# mmt_xbee.net
KiCad netlist of a schematic drawn in EAGLE
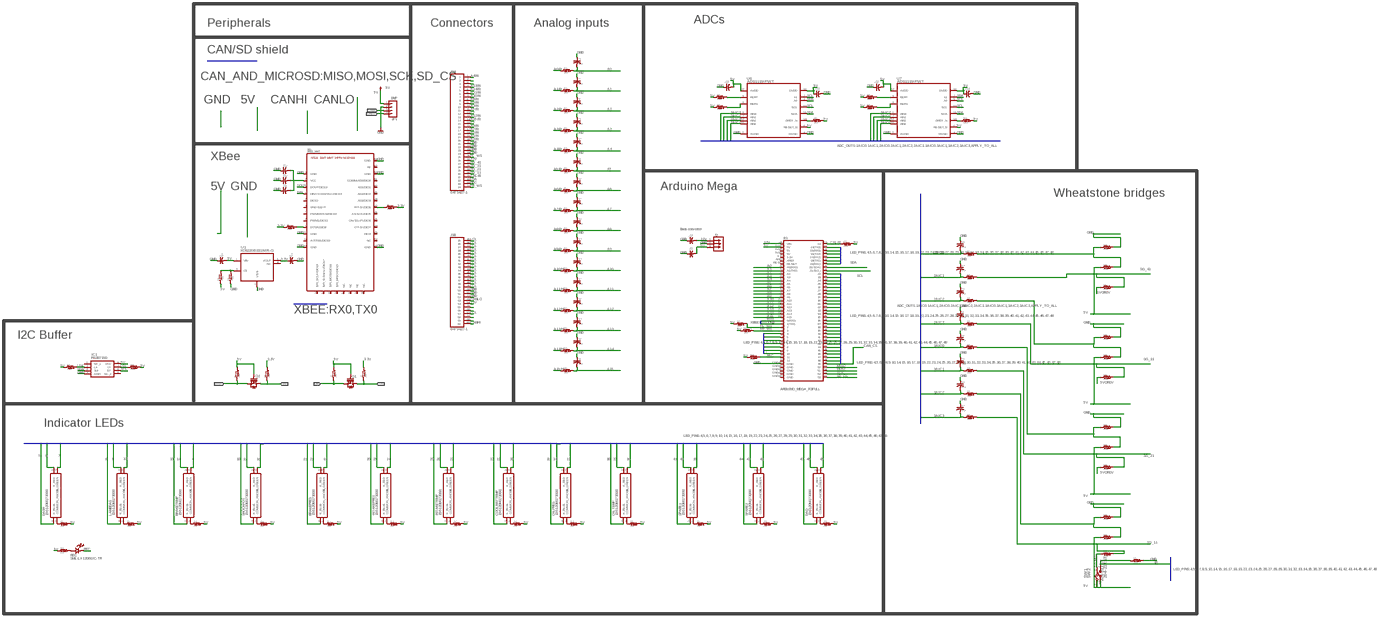
[diagram p0: schematic, sheet 1, overview]
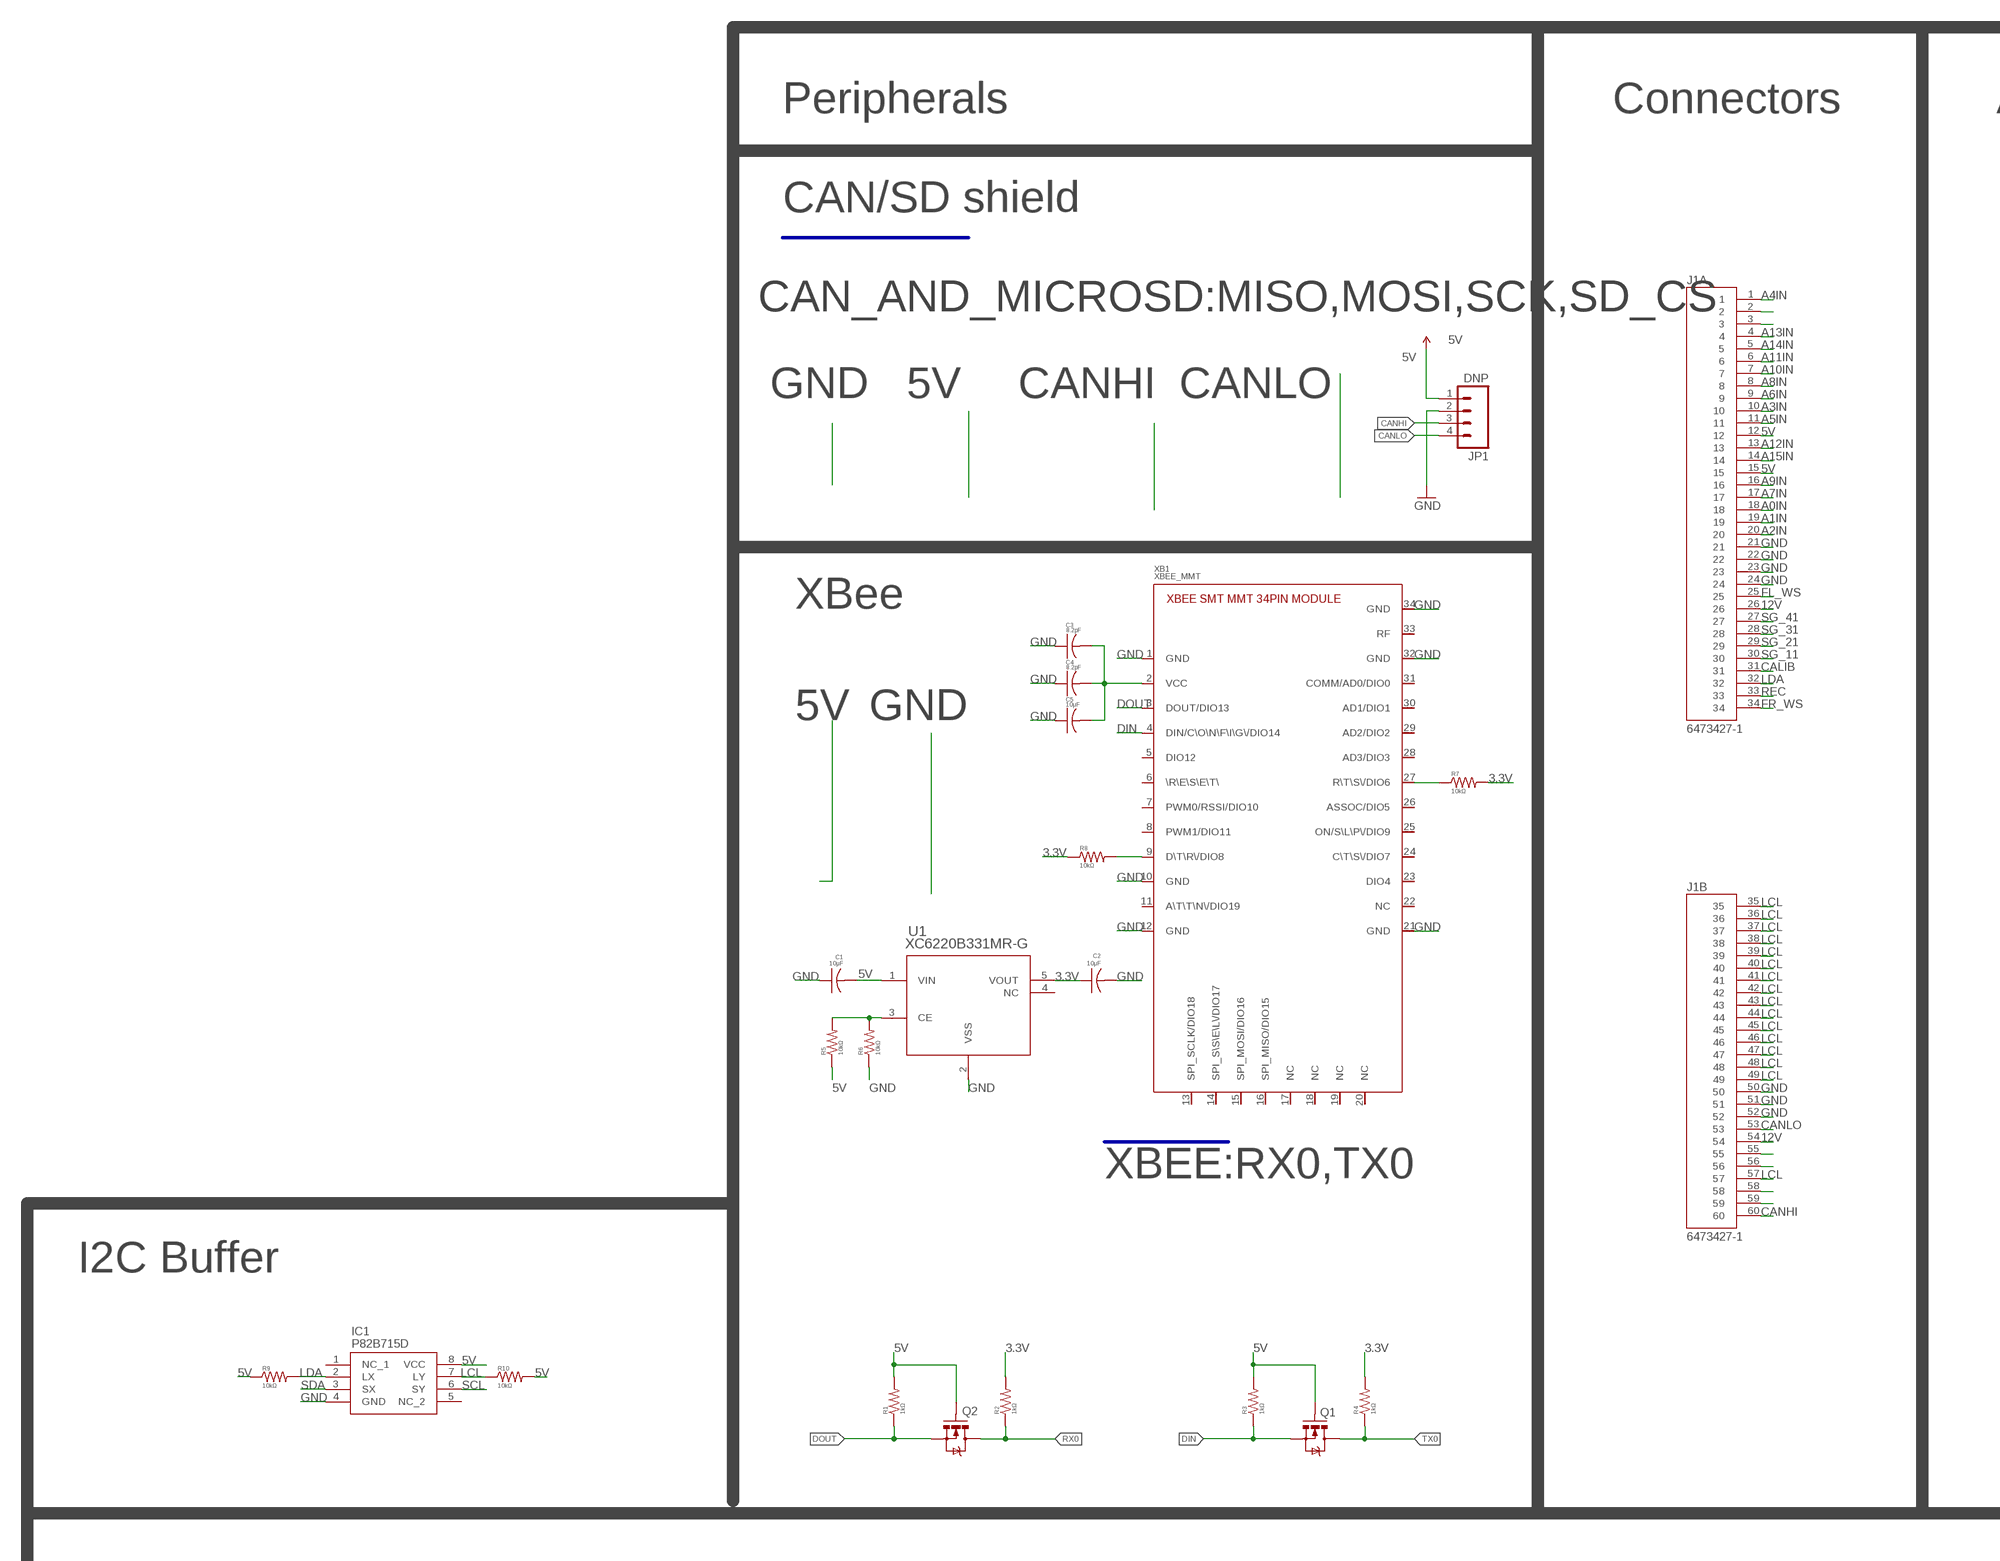
[diagram p1: schematic, sheet 1, part 1 of 5]
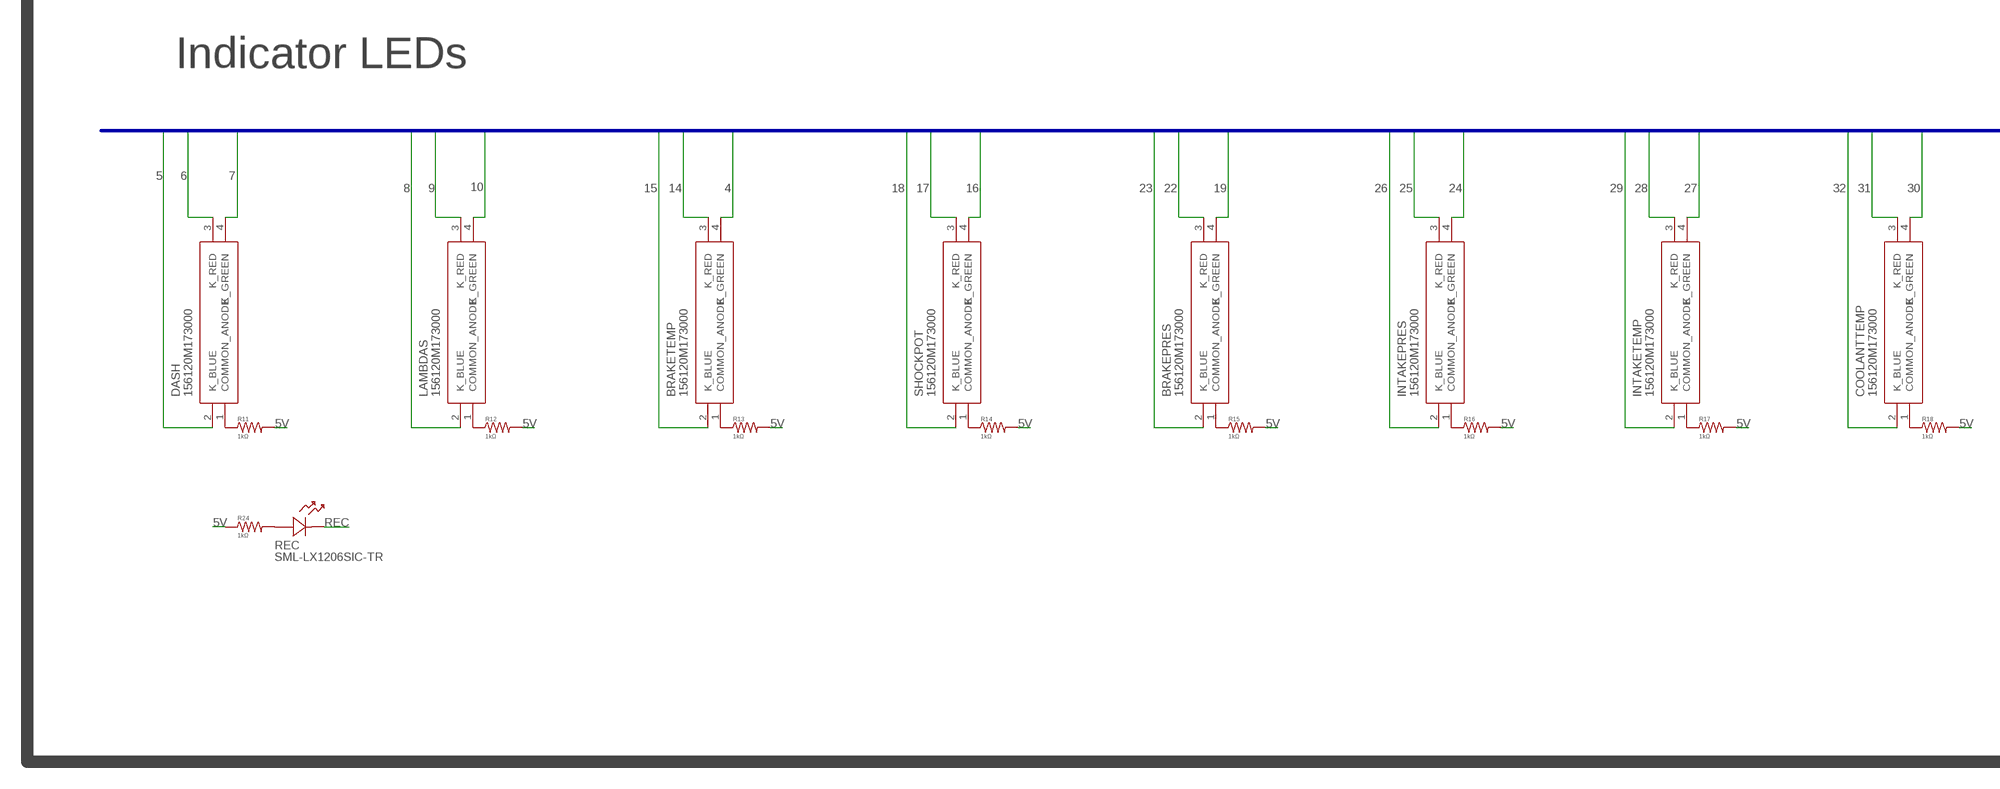
[diagram p2: schematic, sheet 1, part 2 of 5]
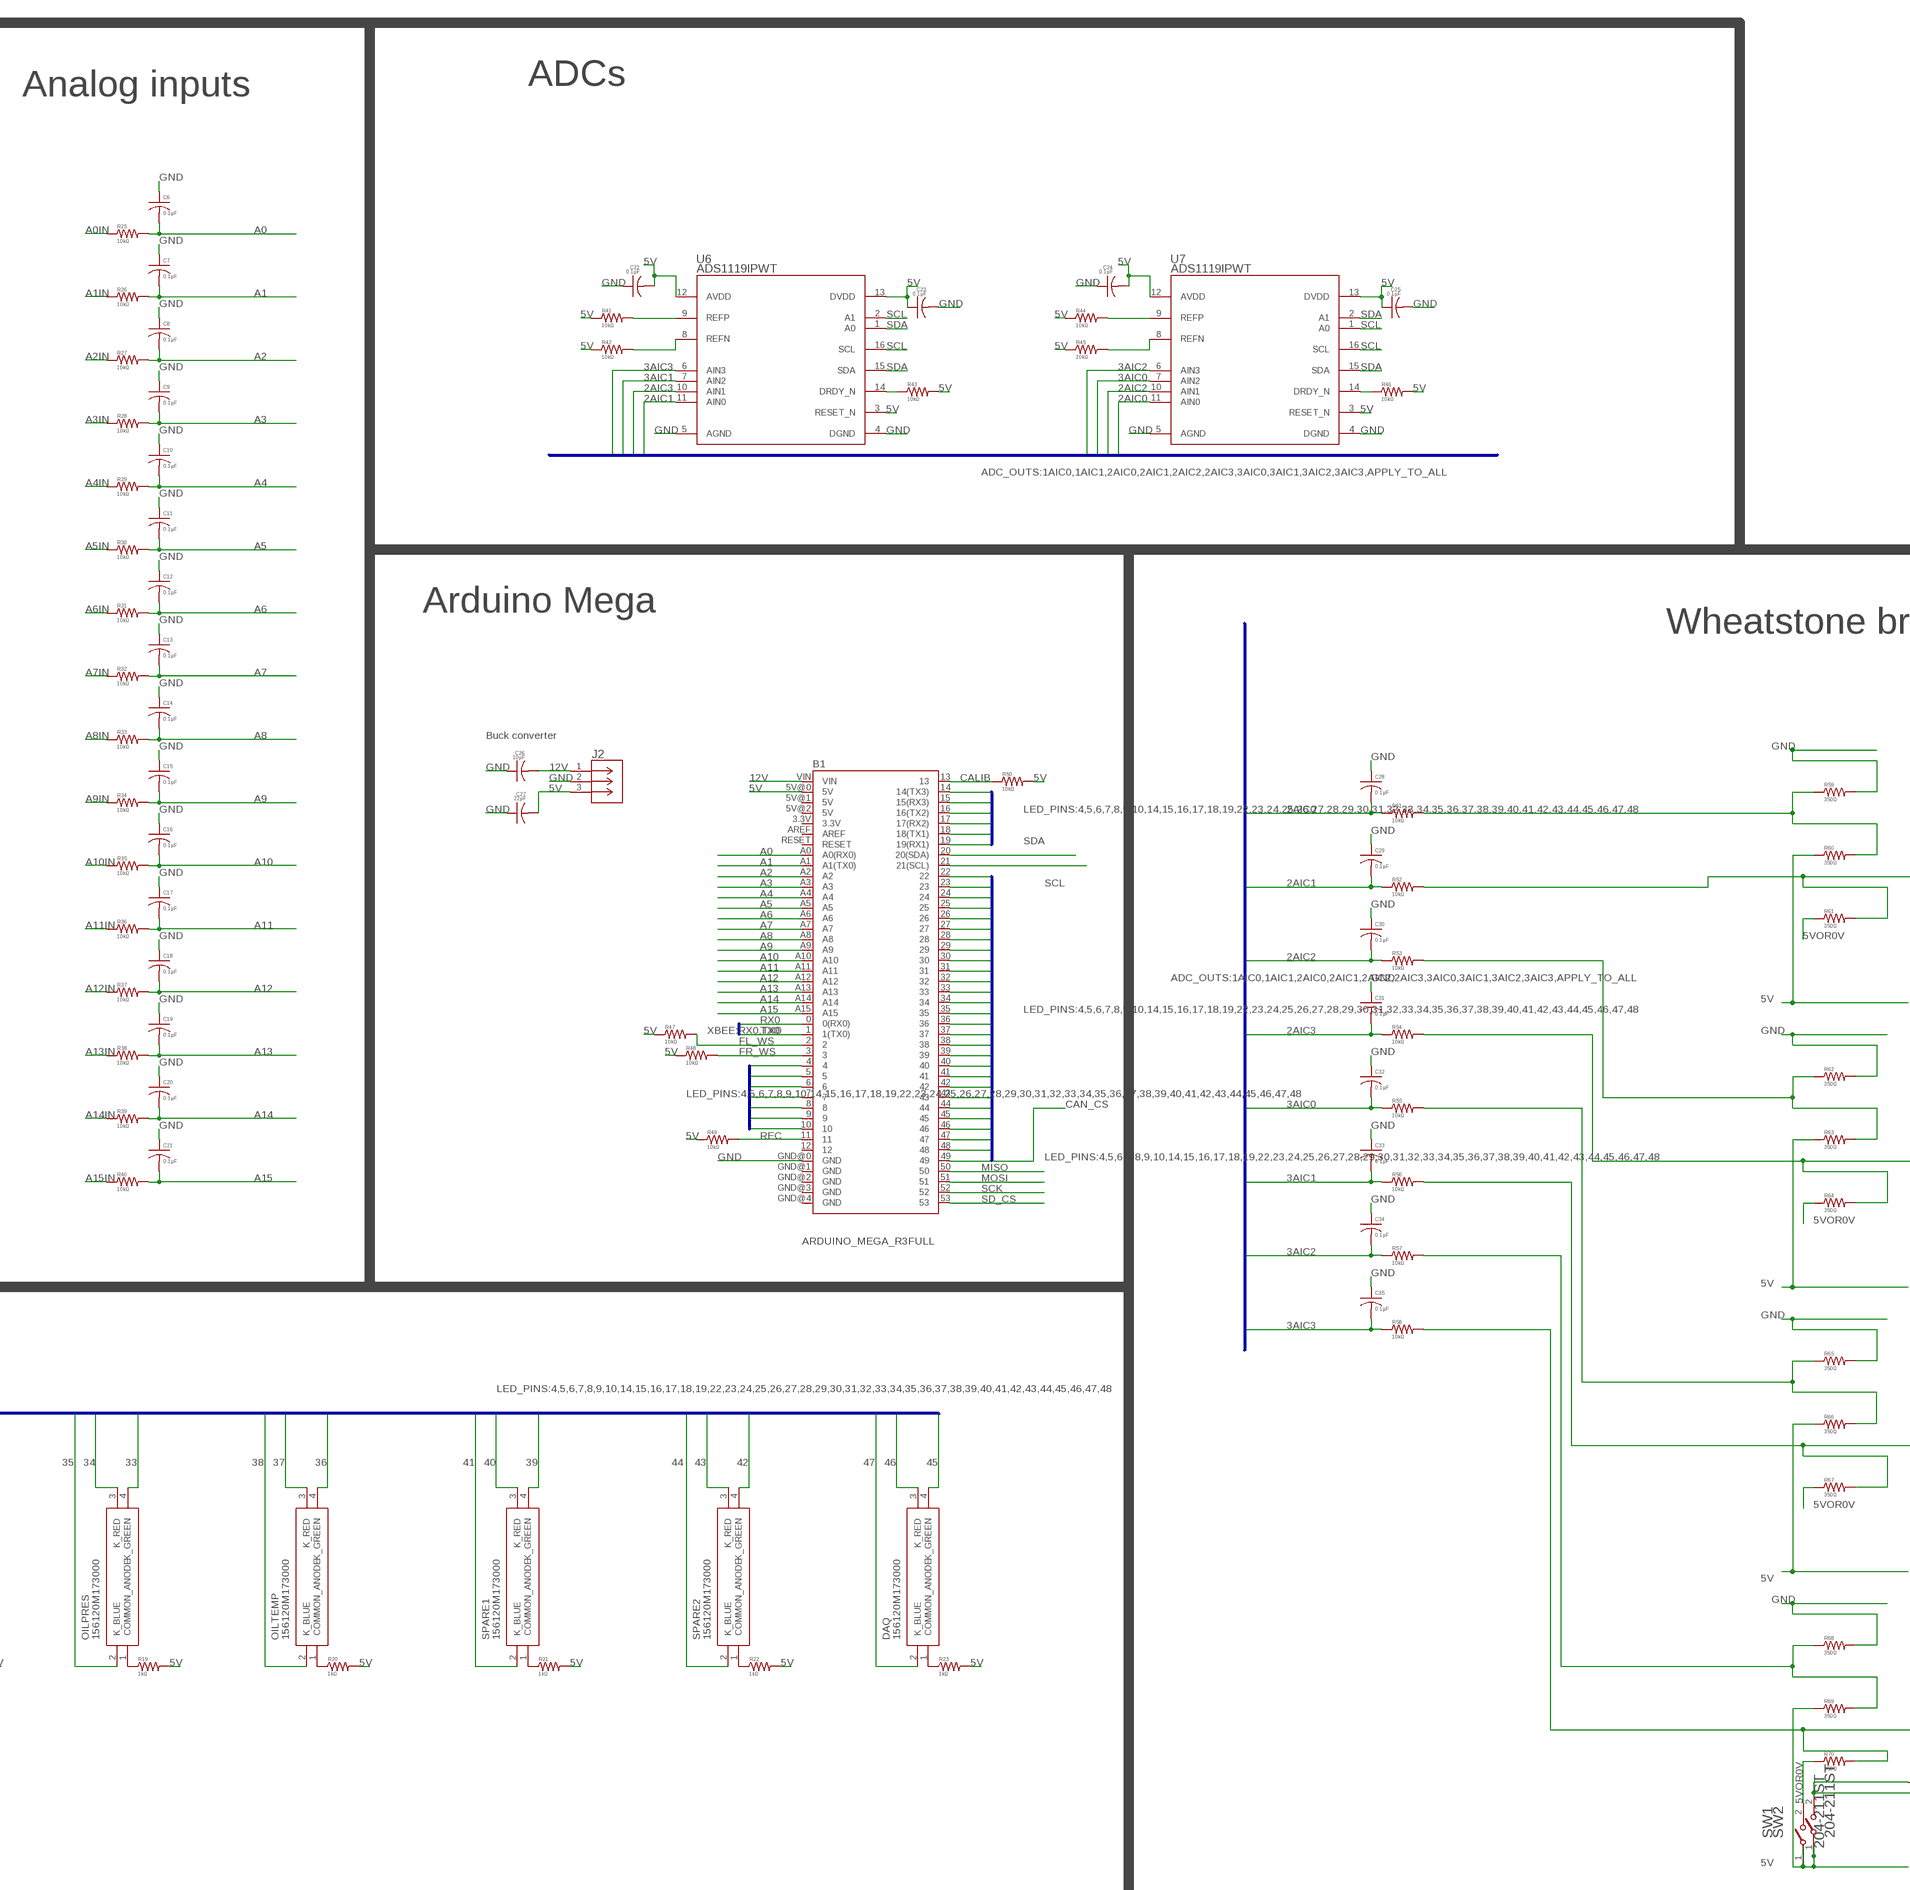
[diagram p3: schematic, sheet 1, part 3 of 5]
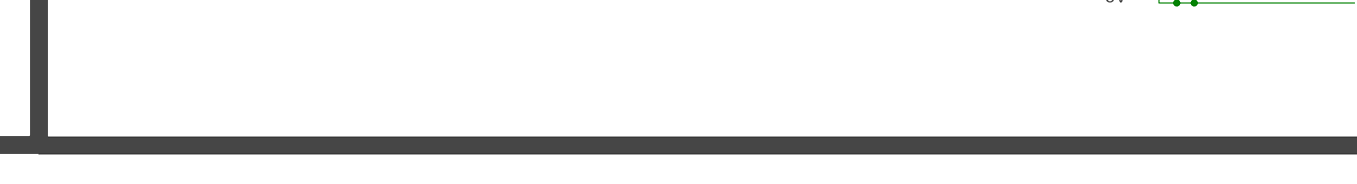
[diagram p4: schematic, sheet 1, part 4 of 5]
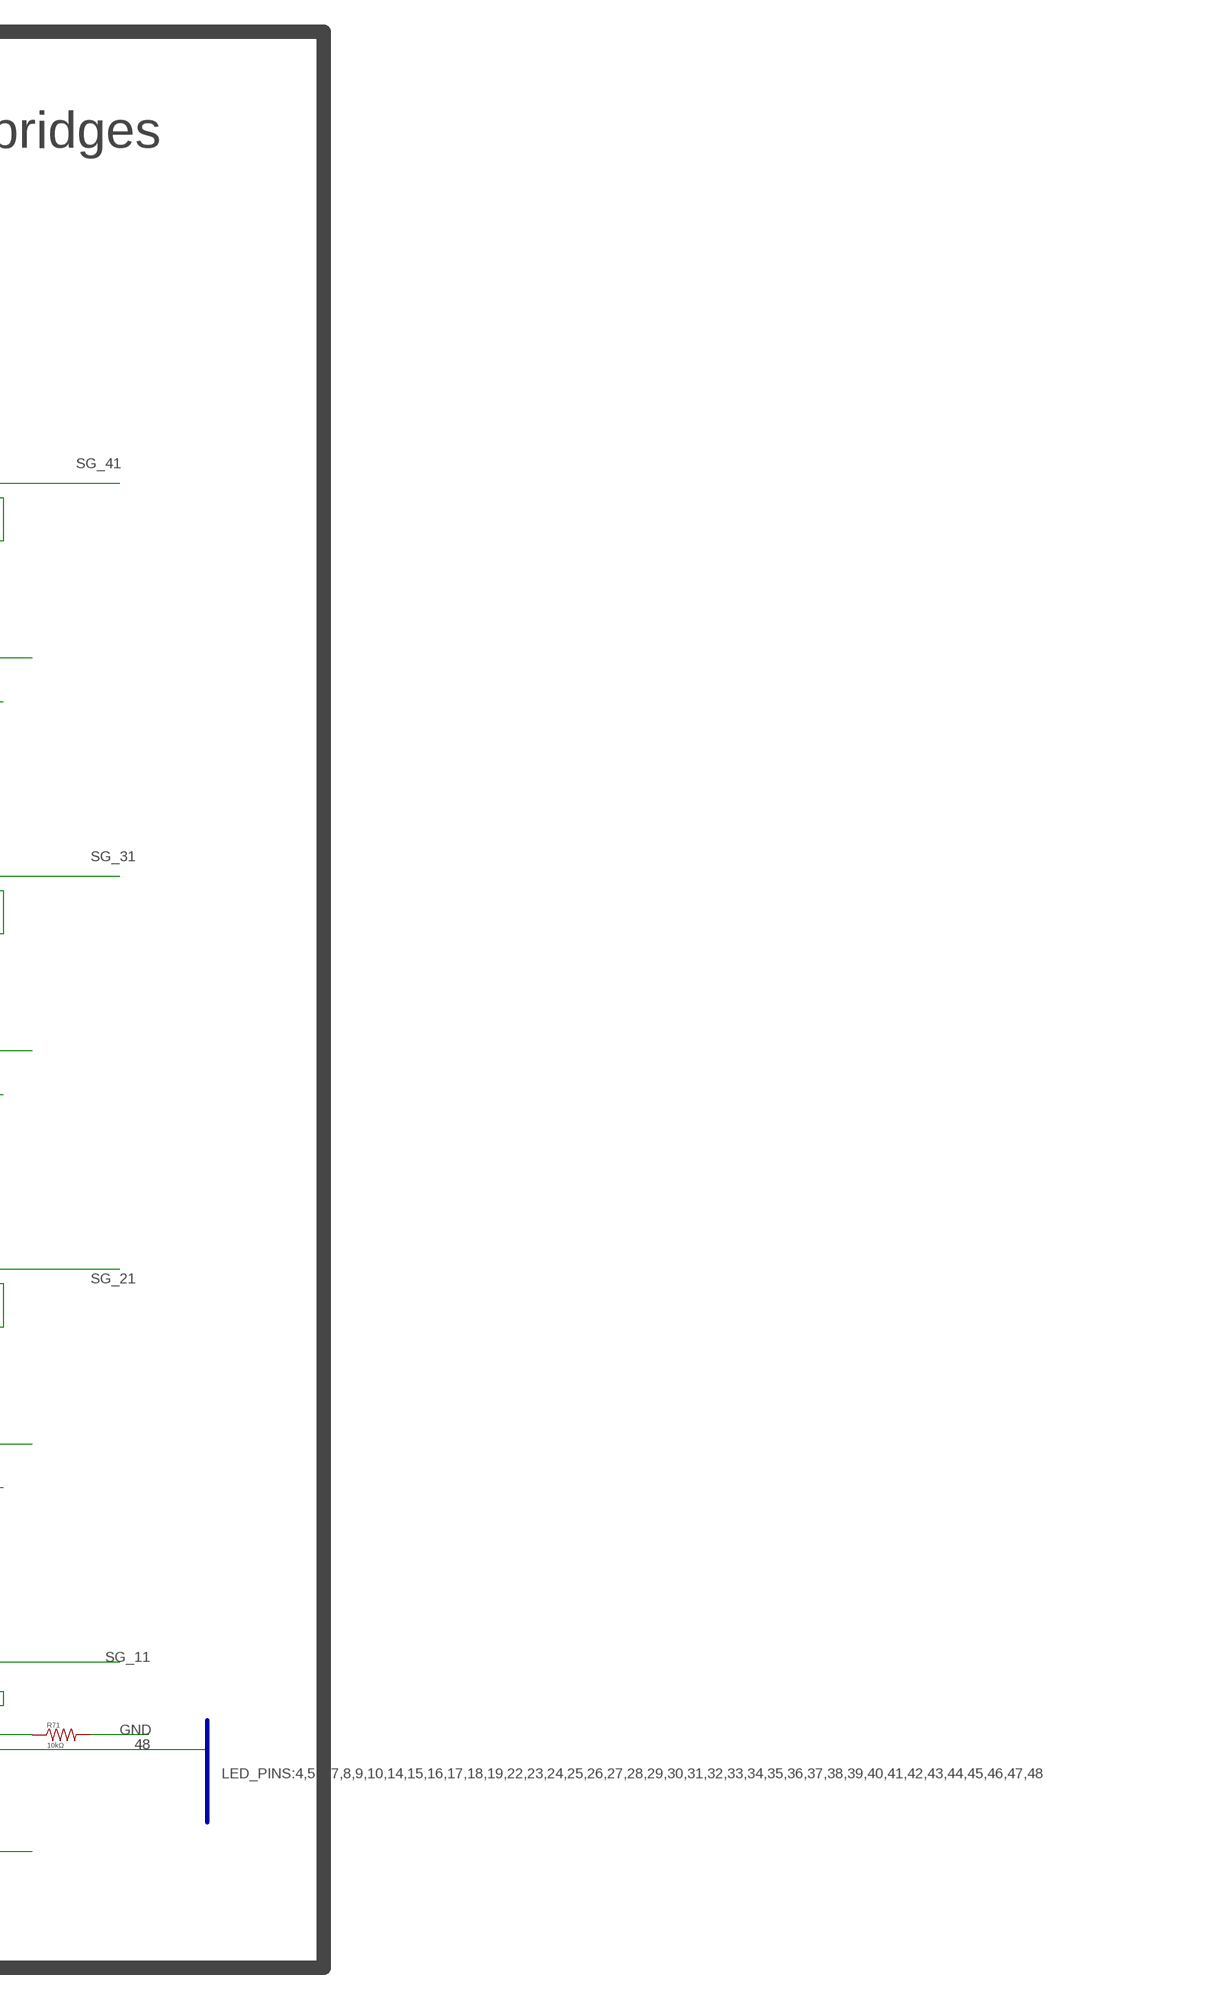
[diagram p5: schematic, sheet 1, part 5 of 5]
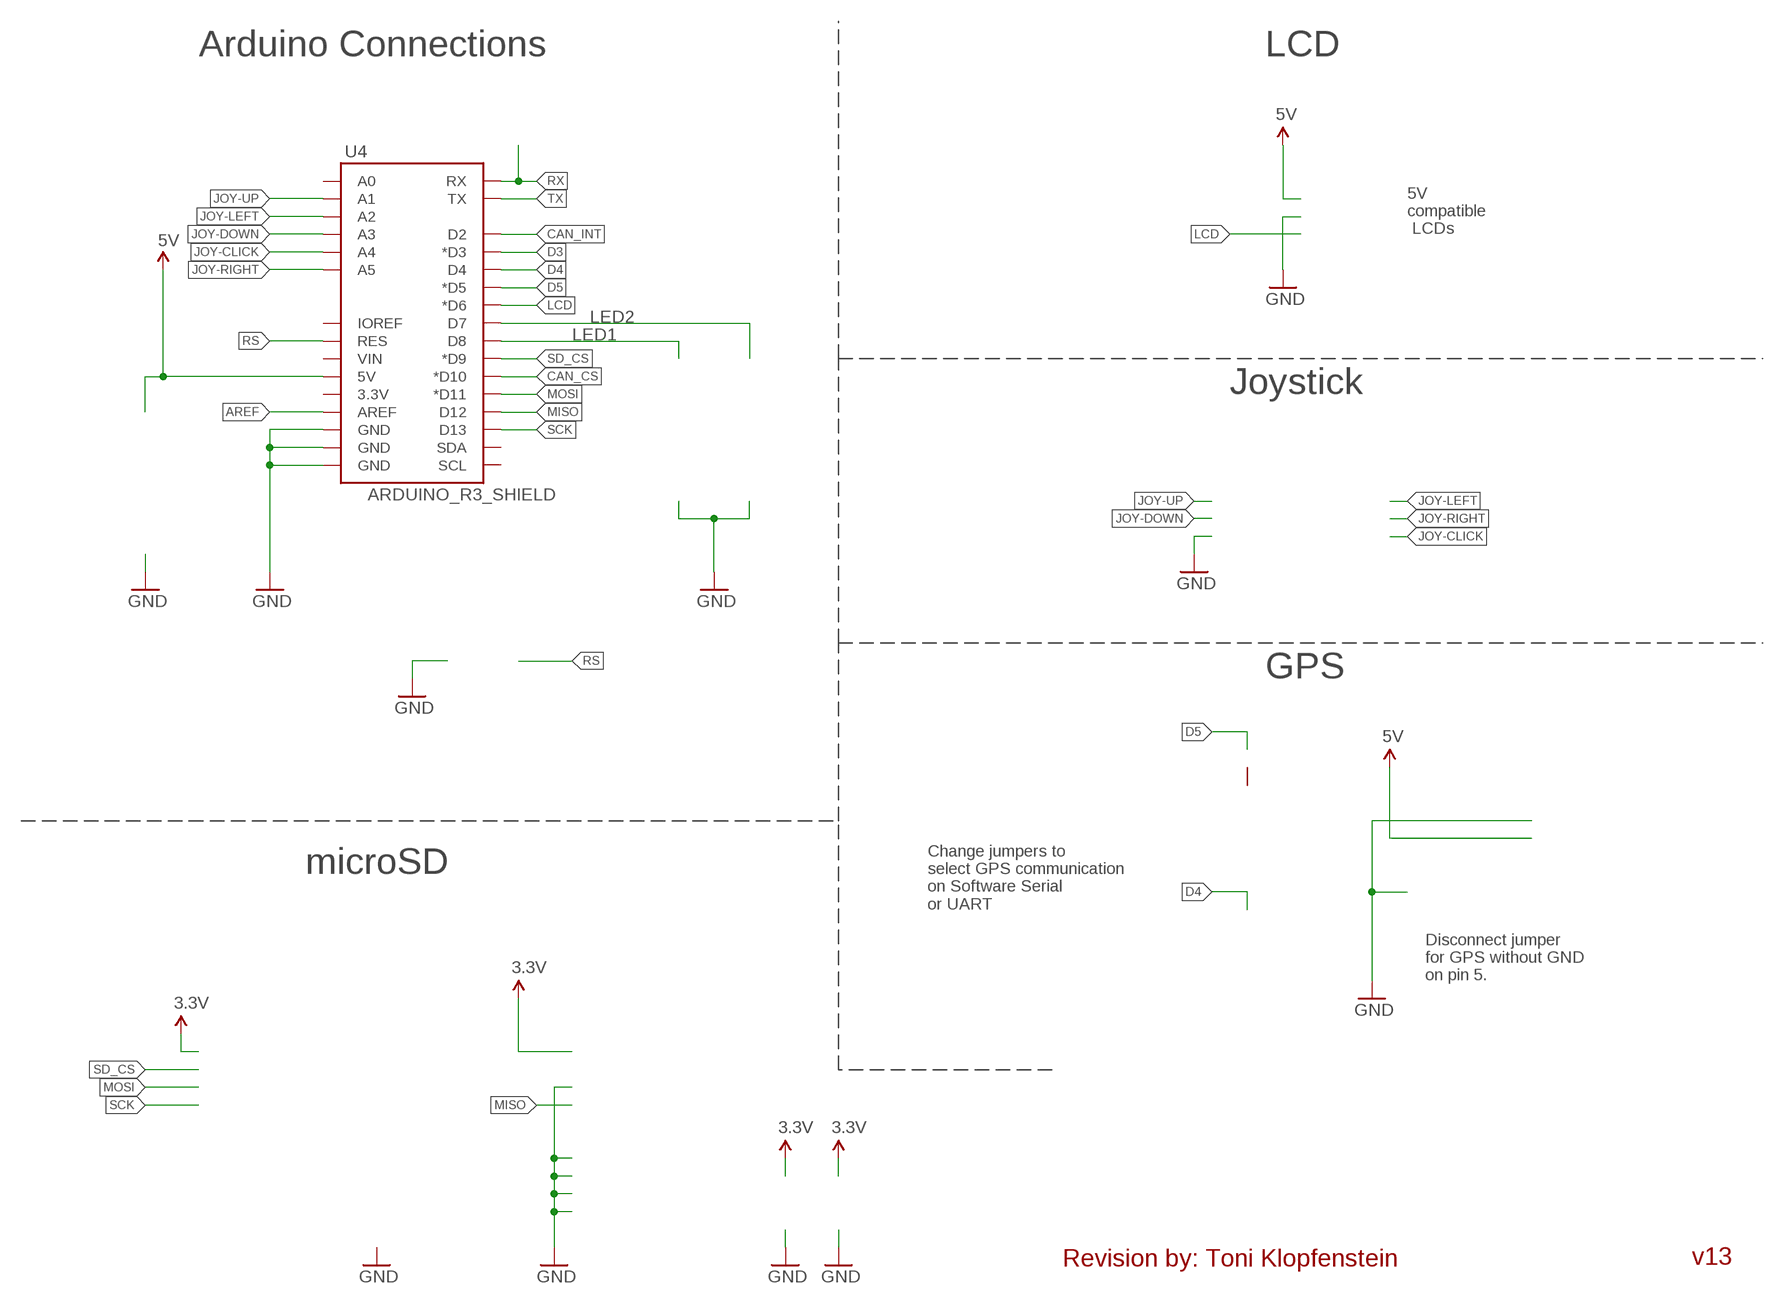
[diagram p6: schematic, sheet 2]

(export (version "E")
  (design (tool "Eeschema 10.0.6"))
  (components
    (comp (ref "B1")
      (value "ARDUINO_MEGA_R3FULL")
      (footprint "eagle-import:ARDUINO_MEGA")
      (libsource (lib "eagle-import") (part "ARDUINO_MEGA_R3FULL"))
    )
    (comp (ref "BRAKEPRES")
      (value "156120M173000")
      (footprint "eagle-import:156120M173000")
      (fields (field (name "MOUSER_PART_NUMBER") "710-156120M173000"))
      (libsource (lib "eagle-import") (part "156120M173000"))
    )
    (comp (ref "BRAKETEMP")
      (value "156120M173000")
      (footprint "eagle-import:156120M173000")
      (fields (field (name "MOUSER_PART_NUMBER") "710-156120M173000"))
      (libsource (lib "eagle-import") (part "156120M173000"))
    )
    (comp (ref "C1")
      (value "10μF")
      (footprint "eagle-import:C1206")
      (libsource (lib "eagle-import") (part "C-USC1206"))
    )
    (comp (ref "C2")
      (value "10μF")
      (footprint "eagle-import:C1206")
      (libsource (lib "eagle-import") (part "C-USC1206"))
    )
    (comp (ref "C3")
      (value "8.2pF")
      (footprint "eagle-import:C1206")
      (libsource (lib "eagle-import") (part "C-USC1206"))
    )
    (comp (ref "C4")
      (value "8.2pF")
      (footprint "eagle-import:C1206")
      (libsource (lib "eagle-import") (part "C-USC1206"))
    )
    (comp (ref "C5")
      (value "10μF")
      (footprint "eagle-import:C1206")
      (libsource (lib "eagle-import") (part "C-USC1206"))
    )
    (comp (ref "C6")
      (value "0.1μF")
      (footprint "eagle-import:C1206")
      (libsource (lib "eagle-import") (part "C-USC1206"))
    )
    (comp (ref "C7")
      (value "0.1μF")
      (footprint "eagle-import:C1206")
      (libsource (lib "eagle-import") (part "C-USC1206"))
    )
    (comp (ref "C8")
      (value "0.1μF")
      (footprint "eagle-import:C1206")
      (libsource (lib "eagle-import") (part "C-USC1206"))
    )
    (comp (ref "C9")
      (value "0.1μF")
      (footprint "eagle-import:C1206")
      (libsource (lib "eagle-import") (part "C-USC1206"))
    )
    (comp (ref "C10")
      (value "0.1μF")
      (footprint "eagle-import:C1206")
      (libsource (lib "eagle-import") (part "C-USC1206"))
    )
    (comp (ref "C11")
      (value "0.1μF")
      (footprint "eagle-import:C1206")
      (libsource (lib "eagle-import") (part "C-USC1206"))
    )
    (comp (ref "C12")
      (value "0.1μF")
      (footprint "eagle-import:C1206")
      (libsource (lib "eagle-import") (part "C-USC1206"))
    )
    (comp (ref "C13")
      (value "0.1μF")
      (footprint "eagle-import:C1206")
      (libsource (lib "eagle-import") (part "C-USC1206"))
    )
    (comp (ref "C14")
      (value "0.1μF")
      (footprint "eagle-import:C1206")
      (libsource (lib "eagle-import") (part "C-USC1206"))
    )
    (comp (ref "C15")
      (value "0.1μF")
      (footprint "eagle-import:C1206")
      (libsource (lib "eagle-import") (part "C-USC1206"))
    )
    (comp (ref "C16")
      (value "0.1μF")
      (footprint "eagle-import:C1206")
      (libsource (lib "eagle-import") (part "C-USC1206"))
    )
    (comp (ref "C17")
      (value "0.1μF")
      (footprint "eagle-import:C1206")
      (libsource (lib "eagle-import") (part "C-USC1206"))
    )
    (comp (ref "C18")
      (value "0.1μF")
      (footprint "eagle-import:C1206")
      (libsource (lib "eagle-import") (part "C-USC1206"))
    )
    (comp (ref "C19")
      (value "0.1μF")
      (footprint "eagle-import:C1206")
      (libsource (lib "eagle-import") (part "C-USC1206"))
    )
    (comp (ref "C20")
      (value "0.1μF")
      (footprint "eagle-import:C1206")
      (libsource (lib "eagle-import") (part "C-USC1206"))
    )
    (comp (ref "C21")
      (value "0.1μF")
      (footprint "eagle-import:C1206")
      (libsource (lib "eagle-import") (part "C-USC1206"))
    )
    (comp (ref "C22")
      (value "0.1μF")
      (footprint "eagle-import:C1206")
      (libsource (lib "eagle-import") (part "C-USC1206"))
    )
    (comp (ref "C23")
      (value "0.1μF")
      (footprint "eagle-import:C1206")
      (libsource (lib "eagle-import") (part "C-USC1206"))
    )
    (comp (ref "C24")
      (value "0.1μF")
      (footprint "eagle-import:C1206")
      (libsource (lib "eagle-import") (part "C-USC1206"))
    )
    (comp (ref "C25")
      (value "0.1μF")
      (footprint "eagle-import:C1206")
      (libsource (lib "eagle-import") (part "C-USC1206"))
    )
    (comp (ref "C26")
      (value "10μF")
      (footprint "eagle-import:C1206")
      (libsource (lib "eagle-import") (part "C-USC1206"))
    )
    (comp (ref "C27")
      (value "22μF")
      (footprint "eagle-import:C1206")
      (libsource (lib "eagle-import") (part "C-USC1206"))
    )
    (comp (ref "C28")
      (value "0.1μF")
      (footprint "eagle-import:C1206")
      (libsource (lib "eagle-import") (part "C-USC1206"))
    )
    (comp (ref "C29")
      (value "0.1μF")
      (footprint "eagle-import:C1206")
      (libsource (lib "eagle-import") (part "C-USC1206"))
    )
    (comp (ref "C30")
      (value "0.1μF")
      (footprint "eagle-import:C1206")
      (libsource (lib "eagle-import") (part "C-USC1206"))
    )
    (comp (ref "C31")
      (value "0.1μF")
      (footprint "eagle-import:C1206")
      (libsource (lib "eagle-import") (part "C-USC1206"))
    )
    (comp (ref "C32")
      (value "0.1μF")
      (footprint "eagle-import:C1206")
      (libsource (lib "eagle-import") (part "C-USC1206"))
    )
    (comp (ref "C33")
      (value "0.1μF")
      (footprint "eagle-import:C1206")
      (libsource (lib "eagle-import") (part "C-USC1206"))
    )
    (comp (ref "C34")
      (value "0.1μF")
      (footprint "eagle-import:C1206")
      (libsource (lib "eagle-import") (part "C-USC1206"))
    )
    (comp (ref "C35")
      (value "0.1μF")
      (footprint "eagle-import:C1206")
      (libsource (lib "eagle-import") (part "C-USC1206"))
    )
    (comp (ref "COOLANTTEMP")
      (value "156120M173000")
      (footprint "eagle-import:156120M173000")
      (fields (field (name "MOUSER_PART_NUMBER") "710-156120M173000"))
      (libsource (lib "eagle-import") (part "156120M173000"))
    )
    (comp (ref "DAQ")
      (value "156120M173000")
      (footprint "eagle-import:156120M173000")
      (fields (field (name "MOUSER_PART_NUMBER") "710-156120M173000"))
      (libsource (lib "eagle-import") (part "156120M173000"))
    )
    (comp (ref "DASH")
      (value "156120M173000")
      (footprint "eagle-import:156120M173000")
      (fields (field (name "MOUSER_PART_NUMBER") "710-156120M173000"))
      (libsource (lib "eagle-import") (part "156120M173000"))
    )
    (comp (ref "IC1")
      (value "P82B715D")
      (footprint "eagle-import:SOIC127P600X175-8N")
      (fields (field (name "MOUSER_PART_NUMBER") "595-P82B715D"))
      (libsource (lib "eagle-import") (part "P82B715D"))
    )
    (comp (ref "INTAKEPRES")
      (value "156120M173000")
      (footprint "eagle-import:156120M173000")
      (fields (field (name "MOUSER_PART_NUMBER") "710-156120M173000"))
      (libsource (lib "eagle-import") (part "156120M173000"))
    )
    (comp (ref "INTAKETEMP")
      (value "156120M173000")
      (footprint "eagle-import:156120M173000")
      (fields (field (name "MOUSER_PART_NUMBER") "710-156120M173000"))
      (libsource (lib "eagle-import") (part "156120M173000"))
    )
    (comp (ref "J1")
      (value "6473427-1")
      (footprint "eagle-import:TE_6473427-1")
      (fields (field (name "MF") "TE Connectivity"))
      (libsource (lib "eagle-import") (part "6473427-1"))
    )
    (comp (ref "J2")
      (value "VR10S05")
      (footprint "eagle-import:CONN3_10S05_XPP")
      (fields (field (name "COPYRIGHT") "Copyright (C) 2022 Ultra Librarian. All rights reserved."))
      (libsource (lib "eagle-import") (part "VR10S05"))
    )
    (comp (ref "JP1")
      (value "DNP")
      (footprint "eagle-import:1X04")
      (libsource (lib "eagle-import") (part "M04PTH"))
    )
    (comp (ref "LAMBDAS")
      (value "156120M173000")
      (footprint "eagle-import:156120M173000")
      (fields (field (name "MOUSER_PART_NUMBER") "710-156120M173000"))
      (libsource (lib "eagle-import") (part "156120M173000"))
    )
    (comp (ref "OILPRES")
      (value "156120M173000")
      (footprint "eagle-import:156120M173000")
      (fields (field (name "MOUSER_PART_NUMBER") "710-156120M173000"))
      (libsource (lib "eagle-import") (part "156120M173000"))
    )
    (comp (ref "OILTEMP")
      (value "156120M173000")
      (footprint "eagle-import:156120M173000")
      (fields (field (name "MOUSER_PART_NUMBER") "710-156120M173000"))
      (libsource (lib "eagle-import") (part "156120M173000"))
    )
    (comp (ref "Q1")
      (value "MOSFET-NCHANNELSMD")
      (footprint "eagle-import:SOT23-3")
      (libsource (lib "eagle-import") (part "MOSFET-NCHANNELSMD"))
    )
    (comp (ref "Q2")
      (value "MOSFET-NCHANNELSMD")
      (footprint "eagle-import:SOT23-3")
      (libsource (lib "eagle-import") (part "MOSFET-NCHANNELSMD"))
    )
    (comp (ref "R1")
      (value "1kΩ")
      (footprint "eagle-import:R1206")
      (libsource (lib "eagle-import") (part "R-US_R1206"))
    )
    (comp (ref "R2")
      (value "1kΩ")
      (footprint "eagle-import:R1206")
      (libsource (lib "eagle-import") (part "R-US_R1206"))
    )
    (comp (ref "R3")
      (value "1kΩ")
      (footprint "eagle-import:R1206")
      (libsource (lib "eagle-import") (part "R-US_R1206"))
    )
    (comp (ref "R4")
      (value "1kΩ")
      (footprint "eagle-import:R1206")
      (libsource (lib "eagle-import") (part "R-US_R1206"))
    )
    (comp (ref "R5")
      (value "10kΩ")
      (footprint "eagle-import:R1206")
      (libsource (lib "eagle-import") (part "R-US_R1206"))
    )
    (comp (ref "R6")
      (value "10kΩ")
      (footprint "eagle-import:R1206")
      (libsource (lib "eagle-import") (part "R-US_R1206"))
    )
    (comp (ref "R7")
      (value "10kΩ")
      (footprint "eagle-import:R1206")
      (libsource (lib "eagle-import") (part "R-US_R1206"))
    )
    (comp (ref "R8")
      (value "10kΩ")
      (footprint "eagle-import:R1206")
      (libsource (lib "eagle-import") (part "R-US_R1206"))
    )
    (comp (ref "R9")
      (value "10kΩ")
      (footprint "eagle-import:R1206")
      (libsource (lib "eagle-import") (part "R-US_R1206"))
    )
    (comp (ref "R10")
      (value "10kΩ")
      (footprint "eagle-import:R1206")
      (libsource (lib "eagle-import") (part "R-US_R1206"))
    )
    (comp (ref "R11")
      (value "1kΩ")
      (footprint "eagle-import:R1206")
      (libsource (lib "eagle-import") (part "R-US_R1206"))
    )
    (comp (ref "R12")
      (value "1kΩ")
      (footprint "eagle-import:R1206")
      (libsource (lib "eagle-import") (part "R-US_R1206"))
    )
    (comp (ref "R13")
      (value "1kΩ")
      (footprint "eagle-import:R1206")
      (libsource (lib "eagle-import") (part "R-US_R1206"))
    )
    (comp (ref "R14")
      (value "1kΩ")
      (footprint "eagle-import:R1206")
      (libsource (lib "eagle-import") (part "R-US_R1206"))
    )
    (comp (ref "R15")
      (value "1kΩ")
      (footprint "eagle-import:R1206")
      (libsource (lib "eagle-import") (part "R-US_R1206"))
    )
    (comp (ref "R16")
      (value "1kΩ")
      (footprint "eagle-import:R1206")
      (libsource (lib "eagle-import") (part "R-US_R1206"))
    )
    (comp (ref "R17")
      (value "1kΩ")
      (footprint "eagle-import:R1206")
      (libsource (lib "eagle-import") (part "R-US_R1206"))
    )
    (comp (ref "R18")
      (value "1kΩ")
      (footprint "eagle-import:R1206")
      (libsource (lib "eagle-import") (part "R-US_R1206"))
    )
    (comp (ref "R19")
      (value "1kΩ")
      (footprint "eagle-import:R1206")
      (libsource (lib "eagle-import") (part "R-US_R1206"))
    )
    (comp (ref "R20")
      (value "1kΩ")
      (footprint "eagle-import:R1206")
      (libsource (lib "eagle-import") (part "R-US_R1206"))
    )
    (comp (ref "R21")
      (value "1kΩ")
      (footprint "eagle-import:R1206")
      (libsource (lib "eagle-import") (part "R-US_R1206"))
    )
    (comp (ref "R22")
      (value "1kΩ")
      (footprint "eagle-import:R1206")
      (libsource (lib "eagle-import") (part "R-US_R1206"))
    )
    (comp (ref "R23")
      (value "1kΩ")
      (footprint "eagle-import:R1206")
      (libsource (lib "eagle-import") (part "R-US_R1206"))
    )
    (comp (ref "R24")
      (value "1kΩ")
      (footprint "eagle-import:R1206")
      (libsource (lib "eagle-import") (part "R-US_R1206"))
    )
    (comp (ref "R25")
      (value "10kΩ")
      (footprint "eagle-import:R1206")
      (libsource (lib "eagle-import") (part "R-US_R1206"))
    )
    (comp (ref "R26")
      (value "10kΩ")
      (footprint "eagle-import:R1206")
      (libsource (lib "eagle-import") (part "R-US_R1206"))
    )
    (comp (ref "R27")
      (value "10kΩ")
      (footprint "eagle-import:R1206")
      (libsource (lib "eagle-import") (part "R-US_R1206"))
    )
    (comp (ref "R28")
      (value "10kΩ")
      (footprint "eagle-import:R1206")
      (libsource (lib "eagle-import") (part "R-US_R1206"))
    )
    (comp (ref "R29")
      (value "10kΩ")
      (footprint "eagle-import:R1206")
      (libsource (lib "eagle-import") (part "R-US_R1206"))
    )
    (comp (ref "R30")
      (value "10kΩ")
      (footprint "eagle-import:R1206")
      (libsource (lib "eagle-import") (part "R-US_R1206"))
    )
    (comp (ref "R31")
      (value "10kΩ")
      (footprint "eagle-import:R1206")
      (libsource (lib "eagle-import") (part "R-US_R1206"))
    )
    (comp (ref "R32")
      (value "10kΩ")
      (footprint "eagle-import:R1206")
      (libsource (lib "eagle-import") (part "R-US_R1206"))
    )
    (comp (ref "R33")
      (value "10kΩ")
      (footprint "eagle-import:R1206")
      (libsource (lib "eagle-import") (part "R-US_R1206"))
    )
    (comp (ref "R34")
      (value "10kΩ")
      (footprint "eagle-import:R1206")
      (libsource (lib "eagle-import") (part "R-US_R1206"))
    )
    (comp (ref "R35")
      (value "10kΩ")
      (footprint "eagle-import:R1206")
      (libsource (lib "eagle-import") (part "R-US_R1206"))
    )
    (comp (ref "R36")
      (value "10kΩ")
      (footprint "eagle-import:R1206")
      (libsource (lib "eagle-import") (part "R-US_R1206"))
    )
    (comp (ref "R37")
      (value "10kΩ")
      (footprint "eagle-import:R1206")
      (libsource (lib "eagle-import") (part "R-US_R1206"))
    )
    (comp (ref "R38")
      (value "10kΩ")
      (footprint "eagle-import:R1206")
      (libsource (lib "eagle-import") (part "R-US_R1206"))
    )
    (comp (ref "R39")
      (value "10kΩ")
      (footprint "eagle-import:R1206")
      (libsource (lib "eagle-import") (part "R-US_R1206"))
    )
    (comp (ref "R40")
      (value "10kΩ")
      (footprint "eagle-import:R1206")
      (libsource (lib "eagle-import") (part "R-US_R1206"))
    )
    (comp (ref "R41")
      (value "10kΩ")
      (footprint "eagle-import:R1206")
      (libsource (lib "eagle-import") (part "R-US_R1206"))
    )
    (comp (ref "R42")
      (value "10kΩ")
      (footprint "eagle-import:R1206")
      (libsource (lib "eagle-import") (part "R-US_R1206"))
    )
    (comp (ref "R43")
      (value "10kΩ")
      (footprint "eagle-import:R1206")
      (libsource (lib "eagle-import") (part "R-US_R1206"))
    )
    (comp (ref "R44")
      (value "10kΩ")
      (footprint "eagle-import:R1206")
      (libsource (lib "eagle-import") (part "R-US_R1206"))
    )
    (comp (ref "R45")
      (value "10kΩ")
      (footprint "eagle-import:R1206")
      (libsource (lib "eagle-import") (part "R-US_R1206"))
    )
    (comp (ref "R46")
      (value "10kΩ")
      (footprint "eagle-import:R1206")
      (libsource (lib "eagle-import") (part "R-US_R1206"))
    )
    (comp (ref "R47")
      (value "10kΩ")
      (footprint "eagle-import:R1206")
      (libsource (lib "eagle-import") (part "R-US_R1206"))
    )
    (comp (ref "R48")
      (value "10kΩ")
      (footprint "eagle-import:R1206")
      (libsource (lib "eagle-import") (part "R-US_R1206"))
    )
    (comp (ref "R49")
      (value "10kΩ")
      (footprint "eagle-import:R1206")
      (libsource (lib "eagle-import") (part "R-US_R1206"))
    )
    (comp (ref "R50")
      (value "10kΩ")
      (footprint "eagle-import:R1206")
      (libsource (lib "eagle-import") (part "R-US_R1206"))
    )
    (comp (ref "R51")
      (value "10kΩ")
      (footprint "eagle-import:R1206")
      (libsource (lib "eagle-import") (part "R-US_R1206"))
    )
    (comp (ref "R52")
      (value "10kΩ")
      (footprint "eagle-import:R1206")
      (libsource (lib "eagle-import") (part "R-US_R1206"))
    )
    (comp (ref "R53")
      (value "10kΩ")
      (footprint "eagle-import:R1206")
      (libsource (lib "eagle-import") (part "R-US_R1206"))
    )
    (comp (ref "R54")
      (value "10kΩ")
      (footprint "eagle-import:R1206")
      (libsource (lib "eagle-import") (part "R-US_R1206"))
    )
    (comp (ref "R55")
      (value "10kΩ")
      (footprint "eagle-import:R1206")
      (libsource (lib "eagle-import") (part "R-US_R1206"))
    )
    (comp (ref "R56")
      (value "10kΩ")
      (footprint "eagle-import:R1206")
      (libsource (lib "eagle-import") (part "R-US_R1206"))
    )
    (comp (ref "R57")
      (value "10kΩ")
      (footprint "eagle-import:R1206")
      (libsource (lib "eagle-import") (part "R-US_R1206"))
    )
    (comp (ref "R58")
      (value "10kΩ")
      (footprint "eagle-import:R1206")
      (libsource (lib "eagle-import") (part "R-US_R1206"))
    )
    (comp (ref "R59")
      (value "350Ω")
      (footprint "eagle-import:R1206")
      (libsource (lib "eagle-import") (part "R-US_R1206"))
    )
    (comp (ref "R60")
      (value "350Ω")
      (footprint "eagle-import:R1206")
      (libsource (lib "eagle-import") (part "R-US_R1206"))
    )
    (comp (ref "R61")
      (value "350Ω")
      (footprint "eagle-import:R1206")
      (libsource (lib "eagle-import") (part "R-US_R1206"))
    )
    (comp (ref "R62")
      (value "350Ω")
      (footprint "eagle-import:R1206")
      (libsource (lib "eagle-import") (part "R-US_R1206"))
    )
    (comp (ref "R63")
      (value "350Ω")
      (footprint "eagle-import:R1206")
      (libsource (lib "eagle-import") (part "R-US_R1206"))
    )
    (comp (ref "R64")
      (value "350Ω")
      (footprint "eagle-import:R1206")
      (libsource (lib "eagle-import") (part "R-US_R1206"))
    )
    (comp (ref "R65")
      (value "350Ω")
      (footprint "eagle-import:R1206")
      (libsource (lib "eagle-import") (part "R-US_R1206"))
    )
    (comp (ref "R66")
      (value "350Ω")
      (footprint "eagle-import:R1206")
      (libsource (lib "eagle-import") (part "R-US_R1206"))
    )
    (comp (ref "R67")
      (value "350Ω")
      (footprint "eagle-import:R1206")
      (libsource (lib "eagle-import") (part "R-US_R1206"))
    )
    (comp (ref "R68")
      (value "350Ω")
      (footprint "eagle-import:R1206")
      (libsource (lib "eagle-import") (part "R-US_R1206"))
    )
    (comp (ref "R69")
      (value "350Ω")
      (footprint "eagle-import:R1206")
      (libsource (lib "eagle-import") (part "R-US_R1206"))
    )
    (comp (ref "R70")
      (value "350Ω")
      (footprint "eagle-import:R1206")
      (libsource (lib "eagle-import") (part "R-US_R1206"))
    )
    (comp (ref "R71")
      (value "10kΩ")
      (footprint "eagle-import:R1206")
      (libsource (lib "eagle-import") (part "R-US_R1206"))
    )
    (comp (ref "REC")
      (value "SML-LX1206SIC-TR")
      (footprint "eagle-import:LED_SML-LX1206SIC-TR_LUM")
      (fields (field (name "COPYRIGHT") "Copyright (C) 2021 Ultra Librarian. All rights reserved."))
      (libsource (lib "eagle-import") (part "SML-LX1206SIC-TR"))
    )
    (comp (ref "SHOCKPOT")
      (value "156120M173000")
      (footprint "eagle-import:156120M173000")
      (fields (field (name "MOUSER_PART_NUMBER") "710-156120M173000"))
      (libsource (lib "eagle-import") (part "156120M173000"))
    )
    (comp (ref "SPARE1")
      (value "156120M173000")
      (footprint "eagle-import:156120M173000")
      (fields (field (name "MOUSER_PART_NUMBER") "710-156120M173000"))
      (libsource (lib "eagle-import") (part "156120M173000"))
    )
    (comp (ref "SPARE2")
      (value "156120M173000")
      (footprint "eagle-import:156120M173000")
      (fields (field (name "MOUSER_PART_NUMBER") "710-156120M173000"))
      (libsource (lib "eagle-import") (part "156120M173000"))
    )
    (comp (ref "SW1")
      (value "CTS_ELECTROCOMPONENTS_204-211STCTS_ELECTROCOMPONENTS_204-211ST_0_0")
      (footprint "eagle-import:CTS_ELECTROCOMPONENTS_204-211ST_0")
      (fields
        (field (name "DIGIKEY_PART_NUMBER") "CT3103CT-ND")
        (field (name "MF") "CTS Electrocomponents")
        (field (name "MOUSER_PART_NUMBER") "774-204-211STR")
      )
      (libsource (lib "eagle-import") (part "CTS_ELECTROCOMPONENTS_204-211STCTS_ELECTROCOMPONENTS_204-211ST_0_0"))
    )
    (comp (ref "SW2")
      (value "CTS_ELECTROCOMPONENTS_204-211STCTS_ELECTROCOMPONENTS_204-211ST_0_0")
      (footprint "eagle-import:CTS_ELECTROCOMPONENTS_204-211ST_0")
      (fields
        (field (name "DIGIKEY_PART_NUMBER") "CT3103CT-ND")
        (field (name "MF") "CTS Electrocomponents")
        (field (name "MOUSER_PART_NUMBER") "774-204-211STR")
      )
      (libsource (lib "eagle-import") (part "CTS_ELECTROCOMPONENTS_204-211STCTS_ELECTROCOMPONENTS_204-211ST_0_0"))
    )
    (comp (ref "U1")
      (value "XC6220B331MR-G")
      (footprint "eagle-import:SOT-25_TOR")
      (fields (field (name "COPYRIGHT") "Copyright (C) 2022 Ultra Librarian. All rights reserved."))
      (libsource (lib "eagle-import") (part "XC6220B331MR-G"))
    )
    (comp (ref "U6")
      (value "ADS1119IPWT")
      (footprint "eagle-import:PW0016A_N")
      (fields (field (name "COPYRIGHT") "Copyright (C) 2021 Ultra Librarian. All rights reserved."))
      (libsource (lib "eagle-import") (part "ADS1119IPWT"))
    )
    (comp (ref "U7")
      (value "ADS1119IPWT")
      (footprint "eagle-import:PW0016A_N")
      (fields (field (name "COPYRIGHT") "Copyright (C) 2021 Ultra Librarian. All rights reserved."))
      (libsource (lib "eagle-import") (part "ADS1119IPWT"))
    )
    (comp (ref "XB1")
      (value "XBEE_MMT")
      (footprint "eagle-import:XBEE_MMT")
      (libsource (lib "eagle-import") (part "XBEE_MMT"))
    )
    (comp (ref "U4")
      (value "ARDUINO_R3_SHIELD")
      (footprint "eagle-import:UNO_R3_SHIELD")
      (libsource (lib "eagle-import") (part "ARDUINO_R3_SHIELD"))
    )
  )
  (nets
    (net (code "11") (name "2AIC0") (class "Default")
      (node (ref "C28") (pin "2") (pinfunction "2_2") (pintype "passive"))
      (node (ref "R51") (pin "1") (pinfunction "1_1") (pintype "passive"))
      (node (ref "U7") (pin "11") (pinfunction "AIN0_11") (pintype "input"))
    )
    (net (code "12") (name "2AIC1") (class "Default")
      (node (ref "C29") (pin "2") (pinfunction "2_2") (pintype "passive"))
      (node (ref "R52") (pin "1") (pinfunction "1_1") (pintype "passive"))
      (node (ref "U6") (pin "11") (pinfunction "AIN0_11") (pintype "input"))
    )
    (net (code "13") (name "2AIC2") (class "Default")
      (node (ref "C30") (pin "2") (pinfunction "2_2") (pintype "passive"))
      (node (ref "R53") (pin "1") (pinfunction "1_1") (pintype "passive"))
      (node (ref "U7") (pin "10") (pinfunction "AIN1_10") (pintype "input"))
    )
    (net (code "14") (name "2AIC3") (class "Default")
      (node (ref "C31") (pin "2") (pinfunction "2_2") (pintype "passive"))
      (node (ref "R54") (pin "1") (pinfunction "1_1") (pintype "passive"))
      (node (ref "U6") (pin "10") (pinfunction "AIN1_10") (pintype "input"))
    )
    (net (code "15") (name "3.3V") (class "Default")
      (node (ref "C2") (pin "1") (pinfunction "1_1") (pintype "passive"))
      (node (ref "R2") (pin "2") (pinfunction "2_2") (pintype "passive"))
      (node (ref "R4") (pin "2") (pinfunction "2_2") (pintype "passive"))
      (node (ref "R7") (pin "2") (pinfunction "2_2") (pintype "passive"))
      (node (ref "R8") (pin "1") (pinfunction "1_1") (pintype "passive"))
      (node (ref "U1") (pin "5") (pinfunction "VOUT_5") (pintype "output"))
    )
    (net (code "16") (name "3AIC0") (class "Default")
      (node (ref "C32") (pin "2") (pinfunction "2_2") (pintype "passive"))
      (node (ref "R55") (pin "1") (pinfunction "1_1") (pintype "passive"))
      (node (ref "U7") (pin "7") (pinfunction "AIN2_7") (pintype "input"))
    )
    (net (code "17") (name "3AIC1") (class "Default")
      (node (ref "C33") (pin "2") (pinfunction "2_2") (pintype "passive"))
      (node (ref "R56") (pin "1") (pinfunction "1_1") (pintype "passive"))
      (node (ref "U6") (pin "7") (pinfunction "AIN2_7") (pintype "input"))
    )
    (net (code "18") (name "3AIC2") (class "Default")
      (node (ref "C34") (pin "2") (pinfunction "2_2") (pintype "passive"))
      (node (ref "R57") (pin "1") (pinfunction "1_1") (pintype "passive"))
      (node (ref "U7") (pin "6") (pinfunction "AIN3_6") (pintype "input"))
    )
    (net (code "19") (name "3AIC3") (class "Default")
      (node (ref "C35") (pin "2") (pinfunction "2_2") (pintype "passive"))
      (node (ref "R58") (pin "1") (pinfunction "1_1") (pintype "passive"))
      (node (ref "U6") (pin "6") (pinfunction "AIN3_6") (pintype "input"))
    )
    (net (code "20") (name "4") (class "Default")
      (node (ref "B1") (pin "4") (pinfunction "4_4") (pintype "bidirectional"))
      (node (ref "BRAKETEMP") (pin "4") (pinfunction "K_GREEN_4") (pintype "bidirectional"))
    )
    (net (code "21") (name "5") (class "Default")
      (node (ref "B1") (pin "5") (pinfunction "5_5") (pintype "bidirectional"))
      (node (ref "DASH") (pin "2") (pinfunction "K_BLUE_2") (pintype "bidirectional"))
    )
    (net (code "22") (name "5V") (class "Default")
      (node (ref "B1") (pin "5V@0") (pinfunction "5V_5V@0") (pintype "bidirectional"))
      (node (ref "C1") (pin "2") (pinfunction "2_2") (pintype "passive"))
      (node (ref "C22") (pin "2") (pinfunction "2_2") (pintype "passive"))
      (node (ref "C23") (pin "1") (pinfunction "1_1") (pintype "passive"))
      (node (ref "C24") (pin "2") (pinfunction "2_2") (pintype "passive"))
      (node (ref "C25") (pin "1") (pinfunction "1_1") (pintype "passive"))
      (node (ref "C27") (pin "2") (pinfunction "2_2") (pintype "passive"))
      (node (ref "IC1") (pin "8") (pinfunction "VCC_8") (pintype "bidirectional"))
      (node (ref "J1") (pin "12") (pinfunction "12_12") (pintype "passive"))
      (node (ref "J1") (pin "15") (pinfunction "15_15") (pintype "passive"))
      (node (ref "J2") (pin "3") (pinfunction "3_3") (pintype "passive"))
      (node (ref "JP1") (pin "1") (pinfunction "1_1") (pintype "passive"))
      (node (ref "Q1") (pin "1") (pinfunction "G_1") (pintype "passive"))
      (node (ref "Q2") (pin "1") (pinfunction "G_1") (pintype "passive"))
      (node (ref "R1") (pin "2") (pinfunction "2_2") (pintype "passive"))
      (node (ref "R10") (pin "2") (pinfunction "2_2") (pintype "passive"))
      (node (ref "R11") (pin "2") (pinfunction "2_2") (pintype "passive"))
      (node (ref "R12") (pin "2") (pinfunction "2_2") (pintype "passive"))
      (node (ref "R13") (pin "2") (pinfunction "2_2") (pintype "passive"))
      (node (ref "R14") (pin "2") (pinfunction "2_2") (pintype "passive"))
      (node (ref "R15") (pin "2") (pinfunction "2_2") (pintype "passive"))
      (node (ref "R16") (pin "2") (pinfunction "2_2") (pintype "passive"))
      (node (ref "R17") (pin "2") (pinfunction "2_2") (pintype "passive"))
      (node (ref "R18") (pin "2") (pinfunction "2_2") (pintype "passive"))
      (node (ref "R19") (pin "2") (pinfunction "2_2") (pintype "passive"))
      (node (ref "R20") (pin "2") (pinfunction "2_2") (pintype "passive"))
      (node (ref "R21") (pin "2") (pinfunction "2_2") (pintype "passive"))
      (node (ref "R22") (pin "2") (pinfunction "2_2") (pintype "passive"))
      (node (ref "R23") (pin "2") (pinfunction "2_2") (pintype "passive"))
      (node (ref "R24") (pin "1") (pinfunction "1_1") (pintype "passive"))
      (node (ref "R3") (pin "2") (pinfunction "2_2") (pintype "passive"))
      (node (ref "R41") (pin "1") (pinfunction "1_1") (pintype "passive"))
      (node (ref "R42") (pin "1") (pinfunction "1_1") (pintype "passive"))
      (node (ref "R43") (pin "2") (pinfunction "2_2") (pintype "passive"))
      (node (ref "R44") (pin "1") (pinfunction "1_1") (pintype "passive"))
      (node (ref "R45") (pin "1") (pinfunction "1_1") (pintype "passive"))
      (node (ref "R46") (pin "2") (pinfunction "2_2") (pintype "passive"))
      (node (ref "R47") (pin "1") (pinfunction "1_1") (pintype "passive"))
      (node (ref "R48") (pin "1") (pinfunction "1_1") (pintype "passive"))
      (node (ref "R49") (pin "1") (pinfunction "1_1") (pintype "passive"))
      (node (ref "R5") (pin "1") (pinfunction "1_1") (pintype "passive"))
      (node (ref "R50") (pin "2") (pinfunction "2_2") (pintype "passive"))
      (node (ref "R60") (pin "1") (pinfunction "1_1") (pintype "passive"))
      (node (ref "R63") (pin "1") (pinfunction "1_1") (pintype "passive"))
      (node (ref "R66") (pin "1") (pinfunction "1_1") (pintype "passive"))
      (node (ref "R69") (pin "1") (pinfunction "1_1") (pintype "passive"))
      (node (ref "R9") (pin "1") (pinfunction "1_1") (pintype "passive"))
      (node (ref "SW1") (pin "1") (pinfunction "1_1") (pintype "passive"))
      (node (ref "SW2") (pin "1") (pinfunction "1_1") (pintype "passive"))
      (node (ref "U1") (pin "1") (pinfunction "VIN_1") (pintype "power_in"))
      (node (ref "U4") (pin "5V") (pinfunction "5V_5V") (pintype "bidirectional"))
      (node (ref "U6") (pin "12") (pinfunction "AVDD_12") (pintype "power_in"))
      (node (ref "U6") (pin "13") (pinfunction "DVDD_13") (pintype "power_in"))
      (node (ref "U6") (pin "3") (pinfunction "RESET_N_3") (pintype "input"))
      (node (ref "U7") (pin "12") (pinfunction "AVDD_12") (pintype "power_in"))
      (node (ref "U7") (pin "13") (pinfunction "DVDD_13") (pintype "power_in"))
      (node (ref "U7") (pin "3") (pinfunction "RESET_N_3") (pintype "input"))
    )
    (net (code "23") (name "5VOR0V") (class "Default")
      (node (ref "R61") (pin "1") (pinfunction "1_1") (pintype "passive"))
      (node (ref "R64") (pin "1") (pinfunction "1_1") (pintype "passive"))
      (node (ref "R67") (pin "1") (pinfunction "1_1") (pintype "passive"))
      (node (ref "R70") (pin "1") (pinfunction "1_1") (pintype "passive"))
      (node (ref "SW1") (pin "2") (pinfunction "2_2") (pintype "passive"))
    )
    (net (code "24") (name "6") (class "Default")
      (node (ref "B1") (pin "6") (pinfunction "6_6") (pintype "bidirectional"))
      (node (ref "DASH") (pin "3") (pinfunction "K_RED_3") (pintype "bidirectional"))
    )
    (net (code "25") (name "7") (class "Default")
      (node (ref "B1") (pin "7") (pinfunction "7_7") (pintype "bidirectional"))
      (node (ref "DASH") (pin "4") (pinfunction "K_GREEN_4") (pintype "bidirectional"))
    )
    (net (code "26") (name "8") (class "Default")
      (node (ref "B1") (pin "8") (pinfunction "8_8") (pintype "bidirectional"))
      (node (ref "LAMBDAS") (pin "2") (pinfunction "K_BLUE_2") (pintype "bidirectional"))
    )
    (net (code "27") (name "9") (class "Default")
      (node (ref "B1") (pin "9") (pinfunction "9_9") (pintype "bidirectional"))
      (node (ref "LAMBDAS") (pin "3") (pinfunction "K_RED_3") (pintype "bidirectional"))
    )
    (net (code "28") (name "10") (class "Default")
      (node (ref "B1") (pin "10") (pinfunction "10_10") (pintype "bidirectional"))
      (node (ref "LAMBDAS") (pin "4") (pinfunction "K_GREEN_4") (pintype "bidirectional"))
    )
    (net (code "29") (name "12V") (class "Default")
      (node (ref "B1") (pin "VIN") (pinfunction "VIN_VIN") (pintype "bidirectional"))
      (node (ref "C26") (pin "2") (pinfunction "2_2") (pintype "passive"))
      (node (ref "J1") (pin "26") (pinfunction "26_26") (pintype "passive"))
      (node (ref "J1") (pin "54") (pinfunction "54_54") (pintype "passive"))
      (node (ref "J2") (pin "1") (pinfunction "1_1") (pintype "passive"))
    )
    (net (code "30") (name "14") (class "Default")
      (node (ref "B1") (pin "14") (pinfunction "14(TX3)_14") (pintype "bidirectional"))
      (node (ref "BRAKETEMP") (pin "3") (pinfunction "K_RED_3") (pintype "bidirectional"))
    )
    (net (code "31") (name "15") (class "Default")
      (node (ref "B1") (pin "15") (pinfunction "15(RX3)_15") (pintype "bidirectional"))
      (node (ref "BRAKETEMP") (pin "2") (pinfunction "K_BLUE_2") (pintype "bidirectional"))
    )
    (net (code "32") (name "16") (class "Default")
      (node (ref "B1") (pin "16") (pinfunction "16(TX2)_16") (pintype "bidirectional"))
      (node (ref "SHOCKPOT") (pin "4") (pinfunction "K_GREEN_4") (pintype "bidirectional"))
    )
    (net (code "33") (name "17") (class "Default")
      (node (ref "B1") (pin "17") (pinfunction "17(RX2)_17") (pintype "bidirectional"))
      (node (ref "SHOCKPOT") (pin "3") (pinfunction "K_RED_3") (pintype "bidirectional"))
    )
    (net (code "34") (name "18") (class "Default")
      (node (ref "B1") (pin "18") (pinfunction "18(TX1)_18") (pintype "bidirectional"))
      (node (ref "SHOCKPOT") (pin "2") (pinfunction "K_BLUE_2") (pintype "bidirectional"))
    )
    (net (code "35") (name "19") (class "Default")
      (node (ref "B1") (pin "19") (pinfunction "19(RX1)_19") (pintype "bidirectional"))
      (node (ref "BRAKEPRES") (pin "4") (pinfunction "K_GREEN_4") (pintype "bidirectional"))
    )
    (net (code "36") (name "22") (class "Default")
      (node (ref "B1") (pin "22") (pinfunction "22_22") (pintype "bidirectional"))
      (node (ref "BRAKEPRES") (pin "3") (pinfunction "K_RED_3") (pintype "bidirectional"))
    )
    (net (code "37") (name "23") (class "Default")
      (node (ref "B1") (pin "23") (pinfunction "23_23") (pintype "bidirectional"))
      (node (ref "BRAKEPRES") (pin "2") (pinfunction "K_BLUE_2") (pintype "bidirectional"))
    )
    (net (code "38") (name "24") (class "Default")
      (node (ref "B1") (pin "24") (pinfunction "24_24") (pintype "bidirectional"))
      (node (ref "INTAKEPRES") (pin "4") (pinfunction "K_GREEN_4") (pintype "bidirectional"))
    )
    (net (code "39") (name "25") (class "Default")
      (node (ref "B1") (pin "25") (pinfunction "25_25") (pintype "bidirectional"))
      (node (ref "INTAKEPRES") (pin "3") (pinfunction "K_RED_3") (pintype "bidirectional"))
    )
    (net (code "40") (name "26") (class "Default")
      (node (ref "B1") (pin "26") (pinfunction "26_26") (pintype "bidirectional"))
      (node (ref "INTAKEPRES") (pin "2") (pinfunction "K_BLUE_2") (pintype "bidirectional"))
    )
    (net (code "41") (name "27") (class "Default")
      (node (ref "B1") (pin "27") (pinfunction "27_27") (pintype "bidirectional"))
      (node (ref "INTAKETEMP") (pin "4") (pinfunction "K_GREEN_4") (pintype "bidirectional"))
    )
    (net (code "42") (name "28") (class "Default")
      (node (ref "B1") (pin "28") (pinfunction "28_28") (pintype "bidirectional"))
      (node (ref "INTAKETEMP") (pin "3") (pinfunction "K_RED_3") (pintype "bidirectional"))
    )
    (net (code "43") (name "29") (class "Default")
      (node (ref "B1") (pin "29") (pinfunction "29_29") (pintype "bidirectional"))
      (node (ref "INTAKETEMP") (pin "2") (pinfunction "K_BLUE_2") (pintype "bidirectional"))
    )
    (net (code "44") (name "30") (class "Default")
      (node (ref "B1") (pin "30") (pinfunction "30_30") (pintype "bidirectional"))
      (node (ref "COOLANTTEMP") (pin "4") (pinfunction "K_GREEN_4") (pintype "bidirectional"))
    )
    (net (code "45") (name "31") (class "Default")
      (node (ref "B1") (pin "31") (pinfunction "31_31") (pintype "bidirectional"))
      (node (ref "COOLANTTEMP") (pin "3") (pinfunction "K_RED_3") (pintype "bidirectional"))
    )
    (net (code "46") (name "32") (class "Default")
      (node (ref "B1") (pin "32") (pinfunction "32_32") (pintype "bidirectional"))
      (node (ref "COOLANTTEMP") (pin "2") (pinfunction "K_BLUE_2") (pintype "bidirectional"))
    )
    (net (code "47") (name "33") (class "Default")
      (node (ref "B1") (pin "33") (pinfunction "33_33") (pintype "bidirectional"))
      (node (ref "OILPRES") (pin "4") (pinfunction "K_GREEN_4") (pintype "bidirectional"))
    )
    (net (code "48") (name "34") (class "Default")
      (node (ref "B1") (pin "34") (pinfunction "34_34") (pintype "bidirectional"))
      (node (ref "OILPRES") (pin "3") (pinfunction "K_RED_3") (pintype "bidirectional"))
    )
    (net (code "49") (name "35") (class "Default")
      (node (ref "B1") (pin "35") (pinfunction "35_35") (pintype "bidirectional"))
      (node (ref "OILPRES") (pin "2") (pinfunction "K_BLUE_2") (pintype "bidirectional"))
    )
    (net (code "50") (name "36") (class "Default")
      (node (ref "B1") (pin "36") (pinfunction "36_36") (pintype "bidirectional"))
      (node (ref "OILTEMP") (pin "4") (pinfunction "K_GREEN_4") (pintype "bidirectional"))
    )
    (net (code "51") (name "37") (class "Default")
      (node (ref "B1") (pin "37") (pinfunction "37_37") (pintype "bidirectional"))
      (node (ref "OILTEMP") (pin "3") (pinfunction "K_RED_3") (pintype "bidirectional"))
    )
    (net (code "52") (name "38") (class "Default")
      (node (ref "B1") (pin "38") (pinfunction "38_38") (pintype "bidirectional"))
      (node (ref "OILTEMP") (pin "2") (pinfunction "K_BLUE_2") (pintype "bidirectional"))
    )
    (net (code "53") (name "39") (class "Default")
      (node (ref "B1") (pin "39") (pinfunction "39_39") (pintype "bidirectional"))
      (node (ref "SPARE1") (pin "4") (pinfunction "K_GREEN_4") (pintype "bidirectional"))
    )
    (net (code "54") (name "40") (class "Default")
      (node (ref "B1") (pin "40") (pinfunction "40_40") (pintype "bidirectional"))
      (node (ref "SPARE1") (pin "3") (pinfunction "K_RED_3") (pintype "bidirectional"))
    )
    (net (code "55") (name "41") (class "Default")
      (node (ref "B1") (pin "41") (pinfunction "41_41") (pintype "bidirectional"))
      (node (ref "SPARE1") (pin "2") (pinfunction "K_BLUE_2") (pintype "bidirectional"))
    )
    (net (code "56") (name "42") (class "Default")
      (node (ref "B1") (pin "42") (pinfunction "42_42") (pintype "bidirectional"))
      (node (ref "SPARE2") (pin "4") (pinfunction "K_GREEN_4") (pintype "bidirectional"))
    )
    (net (code "57") (name "43") (class "Default")
      (node (ref "B1") (pin "43") (pinfunction "43_43") (pintype "bidirectional"))
      (node (ref "SPARE2") (pin "3") (pinfunction "K_RED_3") (pintype "bidirectional"))
    )
    (net (code "58") (name "44") (class "Default")
      (node (ref "B1") (pin "44") (pinfunction "44_44") (pintype "bidirectional"))
      (node (ref "SPARE2") (pin "2") (pinfunction "K_BLUE_2") (pintype "bidirectional"))
    )
    (net (code "59") (name "45") (class "Default")
      (node (ref "B1") (pin "45") (pinfunction "45_45") (pintype "bidirectional"))
      (node (ref "DAQ") (pin "4") (pinfunction "K_GREEN_4") (pintype "bidirectional"))
    )
    (net (code "60") (name "46") (class "Default")
      (node (ref "B1") (pin "46") (pinfunction "46_46") (pintype "bidirectional"))
      (node (ref "DAQ") (pin "3") (pinfunction "K_RED_3") (pintype "bidirectional"))
    )
    (net (code "61") (name "47") (class "Default")
      (node (ref "B1") (pin "47") (pinfunction "47_47") (pintype "bidirectional"))
      (node (ref "DAQ") (pin "2") (pinfunction "K_BLUE_2") (pintype "bidirectional"))
    )
    (net (code "62") (name "48") (class "Default")
      (node (ref "B1") (pin "48") (pinfunction "48_48") (pintype "bidirectional"))
      (node (ref "R71") (pin "1") (pinfunction "1_1") (pintype "passive"))
      (node (ref "SW2") (pin "2") (pinfunction "2_2") (pintype "passive"))
    )
    (net (code "63") (name "A0") (class "Default")
      (node (ref "B1") (pin "A0") (pinfunction "A0(RX0)_A0") (pintype "bidirectional"))
      (node (ref "C6") (pin "2") (pinfunction "2_2") (pintype "passive"))
      (node (ref "R25") (pin "2") (pinfunction "2_2") (pintype "passive"))
    )
    (net (code "64") (name "A0IN") (class "Default")
      (node (ref "J1") (pin "18") (pinfunction "18_18") (pintype "passive"))
      (node (ref "R25") (pin "1") (pinfunction "1_1") (pintype "passive"))
    )
    (net (code "65") (name "A1") (class "Default")
      (node (ref "B1") (pin "A1") (pinfunction "A1(TX0)_A1") (pintype "bidirectional"))
      (node (ref "C7") (pin "2") (pinfunction "2_2") (pintype "passive"))
      (node (ref "R26") (pin "2") (pinfunction "2_2") (pintype "passive"))
    )
    (net (code "66") (name "A1IN") (class "Default")
      (node (ref "J1") (pin "19") (pinfunction "19_19") (pintype "passive"))
      (node (ref "R26") (pin "1") (pinfunction "1_1") (pintype "passive"))
    )
    (net (code "67") (name "A2") (class "Default")
      (node (ref "B1") (pin "A2") (pinfunction "A2_A2") (pintype "bidirectional"))
      (node (ref "C8") (pin "2") (pinfunction "2_2") (pintype "passive"))
      (node (ref "R27") (pin "2") (pinfunction "2_2") (pintype "passive"))
    )
    (net (code "68") (name "A2IN") (class "Default")
      (node (ref "J1") (pin "20") (pinfunction "20_20") (pintype "passive"))
      (node (ref "R27") (pin "1") (pinfunction "1_1") (pintype "passive"))
    )
    (net (code "69") (name "A3") (class "Default")
      (node (ref "B1") (pin "A3") (pinfunction "A3_A3") (pintype "bidirectional"))
      (node (ref "C9") (pin "2") (pinfunction "2_2") (pintype "passive"))
      (node (ref "R28") (pin "2") (pinfunction "2_2") (pintype "passive"))
    )
    (net (code "70") (name "A3IN") (class "Default")
      (node (ref "J1") (pin "10") (pinfunction "10_10") (pintype "passive"))
      (node (ref "R28") (pin "1") (pinfunction "1_1") (pintype "passive"))
    )
    (net (code "71") (name "A4") (class "Default")
      (node (ref "B1") (pin "A4") (pinfunction "A4_A4") (pintype "bidirectional"))
      (node (ref "C10") (pin "2") (pinfunction "2_2") (pintype "passive"))
      (node (ref "R29") (pin "2") (pinfunction "2_2") (pintype "passive"))
    )
    (net (code "72") (name "A4IN") (class "Default")
      (node (ref "J1") (pin "1") (pinfunction "1_1") (pintype "passive"))
      (node (ref "R29") (pin "1") (pinfunction "1_1") (pintype "passive"))
    )
    (net (code "73") (name "A5") (class "Default")
      (node (ref "B1") (pin "A5") (pinfunction "A5_A5") (pintype "bidirectional"))
      (node (ref "C11") (pin "2") (pinfunction "2_2") (pintype "passive"))
      (node (ref "R30") (pin "2") (pinfunction "2_2") (pintype "passive"))
    )
    (net (code "74") (name "A5IN") (class "Default")
      (node (ref "J1") (pin "11") (pinfunction "11_11") (pintype "passive"))
      (node (ref "R30") (pin "1") (pinfunction "1_1") (pintype "passive"))
    )
    (net (code "75") (name "A6") (class "Default")
      (node (ref "B1") (pin "A6") (pinfunction "A6_A6") (pintype "bidirectional"))
      (node (ref "C12") (pin "2") (pinfunction "2_2") (pintype "passive"))
      (node (ref "R31") (pin "2") (pinfunction "2_2") (pintype "passive"))
    )
    (net (code "76") (name "A6IN") (class "Default")
      (node (ref "J1") (pin "9") (pinfunction "9_9") (pintype "passive"))
      (node (ref "R31") (pin "1") (pinfunction "1_1") (pintype "passive"))
    )
    (net (code "77") (name "A7") (class "Default")
      (node (ref "B1") (pin "A7") (pinfunction "A7_A7") (pintype "bidirectional"))
      (node (ref "C13") (pin "2") (pinfunction "2_2") (pintype "passive"))
      (node (ref "R32") (pin "2") (pinfunction "2_2") (pintype "passive"))
    )
    (net (code "78") (name "A7IN") (class "Default")
      (node (ref "J1") (pin "17") (pinfunction "17_17") (pintype "passive"))
      (node (ref "R32") (pin "1") (pinfunction "1_1") (pintype "passive"))
    )
    (net (code "79") (name "A8") (class "Default")
      (node (ref "B1") (pin "A8") (pinfunction "A8_A8") (pintype "bidirectional"))
      (node (ref "C14") (pin "2") (pinfunction "2_2") (pintype "passive"))
      (node (ref "R33") (pin "2") (pinfunction "2_2") (pintype "passive"))
    )
    (net (code "80") (name "A8IN") (class "Default")
      (node (ref "J1") (pin "8") (pinfunction "8_8") (pintype "passive"))
      (node (ref "R33") (pin "1") (pinfunction "1_1") (pintype "passive"))
    )
    (net (code "81") (name "A9") (class "Default")
      (node (ref "B1") (pin "A9") (pinfunction "A9_A9") (pintype "bidirectional"))
      (node (ref "C15") (pin "2") (pinfunction "2_2") (pintype "passive"))
      (node (ref "R34") (pin "2") (pinfunction "2_2") (pintype "passive"))
    )
    (net (code "82") (name "A9IN") (class "Default")
      (node (ref "J1") (pin "16") (pinfunction "16_16") (pintype "passive"))
      (node (ref "R34") (pin "1") (pinfunction "1_1") (pintype "passive"))
    )
    (net (code "83") (name "A10") (class "Default")
      (node (ref "B1") (pin "A10") (pinfunction "A10_A10") (pintype "bidirectional"))
      (node (ref "C16") (pin "2") (pinfunction "2_2") (pintype "passive"))
      (node (ref "R35") (pin "2") (pinfunction "2_2") (pintype "passive"))
    )
    (net (code "84") (name "A10IN") (class "Default")
      (node (ref "J1") (pin "7") (pinfunction "7_7") (pintype "passive"))
      (node (ref "R35") (pin "1") (pinfunction "1_1") (pintype "passive"))
    )
    (net (code "85") (name "A11") (class "Default")
      (node (ref "B1") (pin "A11") (pinfunction "A11_A11") (pintype "bidirectional"))
      (node (ref "C17") (pin "2") (pinfunction "2_2") (pintype "passive"))
      (node (ref "R36") (pin "2") (pinfunction "2_2") (pintype "passive"))
    )
    (net (code "86") (name "A11IN") (class "Default")
      (node (ref "J1") (pin "6") (pinfunction "6_6") (pintype "passive"))
      (node (ref "R36") (pin "1") (pinfunction "1_1") (pintype "passive"))
    )
    (net (code "87") (name "A12") (class "Default")
      (node (ref "B1") (pin "A12") (pinfunction "A12_A12") (pintype "bidirectional"))
      (node (ref "C18") (pin "2") (pinfunction "2_2") (pintype "passive"))
      (node (ref "R37") (pin "2") (pinfunction "2_2") (pintype "passive"))
    )
    (net (code "88") (name "A12IN") (class "Default")
      (node (ref "J1") (pin "13") (pinfunction "13_13") (pintype "passive"))
      (node (ref "R37") (pin "1") (pinfunction "1_1") (pintype "passive"))
    )
    (net (code "89") (name "A13") (class "Default")
      (node (ref "B1") (pin "A13") (pinfunction "A13_A13") (pintype "bidirectional"))
      (node (ref "C19") (pin "2") (pinfunction "2_2") (pintype "passive"))
      (node (ref "R38") (pin "2") (pinfunction "2_2") (pintype "passive"))
    )
    (net (code "90") (name "A13IN") (class "Default")
      (node (ref "J1") (pin "4") (pinfunction "4_4") (pintype "passive"))
      (node (ref "R38") (pin "1") (pinfunction "1_1") (pintype "passive"))
    )
    (net (code "91") (name "A14") (class "Default")
      (node (ref "B1") (pin "A14") (pinfunction "A14_A14") (pintype "bidirectional"))
      (node (ref "C20") (pin "2") (pinfunction "2_2") (pintype "passive"))
      (node (ref "R39") (pin "2") (pinfunction "2_2") (pintype "passive"))
    )
    (net (code "92") (name "A14IN") (class "Default")
      (node (ref "J1") (pin "5") (pinfunction "5_5") (pintype "passive"))
      (node (ref "R39") (pin "1") (pinfunction "1_1") (pintype "passive"))
    )
    (net (code "93") (name "A15") (class "Default")
      (node (ref "B1") (pin "A15") (pinfunction "A15_A15") (pintype "bidirectional"))
      (node (ref "C21") (pin "2") (pinfunction "2_2") (pintype "passive"))
      (node (ref "R40") (pin "2") (pinfunction "2_2") (pintype "passive"))
    )
    (net (code "94") (name "A15IN") (class "Default")
      (node (ref "J1") (pin "14") (pinfunction "14_14") (pintype "passive"))
      (node (ref "R40") (pin "1") (pinfunction "1_1") (pintype "passive"))
    )
    (net (code "95") (name "AREF") (class "Default")
      (node (ref "U4") (pin "AREF") (pinfunction "AREF_AREF") (pintype "bidirectional"))
    )
    (net (code "96") (name "CALIB") (class "Default")
      (node (ref "B1") (pin "13") (pinfunction "13_13") (pintype "bidirectional"))
      (node (ref "J1") (pin "31") (pinfunction "31_31") (pintype "passive"))
      (node (ref "R50") (pin "1") (pinfunction "1_1") (pintype "passive"))
    )
    (net (code "97") (name "CANHI") (class "Default")
      (node (ref "J1") (pin "60") (pinfunction "60_60") (pintype "passive"))
      (node (ref "JP1") (pin "3") (pinfunction "3_3") (pintype "passive"))
    )
    (net (code "98") (name "CANLO") (class "Default")
      (node (ref "J1") (pin "53") (pinfunction "53_53") (pintype "passive"))
      (node (ref "JP1") (pin "4") (pinfunction "4_4") (pintype "passive"))
    )
    (net (code "99") (name "CAN_CS") (class "Default")
      (node (ref "B1") (pin "49") (pinfunction "49_49") (pintype "bidirectional"))
      (node (ref "U4") (pin "D10") (pinfunction "*D10_D10") (pintype "bidirectional"))
    )
    (net (code "100") (name "CAN_INT") (class "Default")
      (node (ref "U4") (pin "D2") (pinfunction "D2_D2") (pintype "bidirectional"))
    )
    (net (code "101") (name "D3") (class "Default")
      (node (ref "U4") (pin "D3") (pinfunction "*D3_D3") (pintype "bidirectional"))
    )
    (net (code "102") (name "D4") (class "Default")
      (node (ref "U4") (pin "D4") (pinfunction "D4_D4") (pintype "bidirectional"))
    )
    (net (code "103") (name "D5") (class "Default")
      (node (ref "U4") (pin "D5") (pinfunction "*D5_D5") (pintype "bidirectional"))
    )
    (net (code "104") (name "DIN") (class "Default")
      (node (ref "Q1") (pin "2") (pinfunction "S_2") (pintype "passive"))
      (node (ref "R3") (pin "1") (pinfunction "1_1") (pintype "passive"))
      (node (ref "XB1") (pin "4") (pinfunction "DIN/C\\O\\N\\F\\I\\G\\/DIO14_4") (pintype "passive"))
    )
    (net (code "105") (name "DOUT") (class "Default")
      (node (ref "Q2") (pin "2") (pinfunction "S_2") (pintype "passive"))
      (node (ref "R1") (pin "1") (pinfunction "1_1") (pintype "passive"))
      (node (ref "XB1") (pin "3") (pinfunction "DOUT/DIO13_3") (pintype "passive"))
    )
    (net (code "106") (name "FL_WS") (class "Default")
      (node (ref "B1") (pin "2") (pinfunction "2_2") (pintype "bidirectional"))
      (node (ref "J1") (pin "25") (pinfunction "25_25") (pintype "passive"))
      (node (ref "R47") (pin "2") (pinfunction "2_2") (pintype "passive"))
    )
    (net (code "107") (name "FR_WS") (class "Default")
      (node (ref "B1") (pin "3") (pinfunction "3_3") (pintype "bidirectional"))
      (node (ref "J1") (pin "34") (pinfunction "34_34") (pintype "passive"))
      (node (ref "R48") (pin "2") (pinfunction "2_2") (pintype "passive"))
    )
    (net (code "108") (name "GND") (class "Default")
      (node (ref "B1") (pin "GND@0") (pinfunction "GND_GND@0") (pintype "bidirectional"))
      (node (ref "C1") (pin "1") (pinfunction "1_1") (pintype "passive"))
      (node (ref "C10") (pin "1") (pinfunction "1_1") (pintype "passive"))
      (node (ref "C11") (pin "1") (pinfunction "1_1") (pintype "passive"))
      (node (ref "C12") (pin "1") (pinfunction "1_1") (pintype "passive"))
      (node (ref "C13") (pin "1") (pinfunction "1_1") (pintype "passive"))
      (node (ref "C14") (pin "1") (pinfunction "1_1") (pintype "passive"))
      (node (ref "C15") (pin "1") (pinfunction "1_1") (pintype "passive"))
      (node (ref "C16") (pin "1") (pinfunction "1_1") (pintype "passive"))
      (node (ref "C17") (pin "1") (pinfunction "1_1") (pintype "passive"))
      (node (ref "C18") (pin "1") (pinfunction "1_1") (pintype "passive"))
      (node (ref "C19") (pin "1") (pinfunction "1_1") (pintype "passive"))
      (node (ref "C2") (pin "2") (pinfunction "2_2") (pintype "passive"))
      (node (ref "C20") (pin "1") (pinfunction "1_1") (pintype "passive"))
      (node (ref "C21") (pin "1") (pinfunction "1_1") (pintype "passive"))
      (node (ref "C22") (pin "1") (pinfunction "1_1") (pintype "passive"))
      (node (ref "C23") (pin "2") (pinfunction "2_2") (pintype "passive"))
      (node (ref "C24") (pin "1") (pinfunction "1_1") (pintype "passive"))
      (node (ref "C25") (pin "2") (pinfunction "2_2") (pintype "passive"))
      (node (ref "C26") (pin "1") (pinfunction "1_1") (pintype "passive"))
      (node (ref "C27") (pin "1") (pinfunction "1_1") (pintype "passive"))
      (node (ref "C28") (pin "1") (pinfunction "1_1") (pintype "passive"))
      (node (ref "C29") (pin "1") (pinfunction "1_1") (pintype "passive"))
      (node (ref "C3") (pin "1") (pinfunction "1_1") (pintype "passive"))
      (node (ref "C30") (pin "1") (pinfunction "1_1") (pintype "passive"))
      (node (ref "C31") (pin "1") (pinfunction "1_1") (pintype "passive"))
      (node (ref "C32") (pin "1") (pinfunction "1_1") (pintype "passive"))
      (node (ref "C33") (pin "1") (pinfunction "1_1") (pintype "passive"))
      (node (ref "C34") (pin "1") (pinfunction "1_1") (pintype "passive"))
      (node (ref "C35") (pin "1") (pinfunction "1_1") (pintype "passive"))
      (node (ref "C4") (pin "1") (pinfunction "1_1") (pintype "passive"))
      (node (ref "C5") (pin "1") (pinfunction "1_1") (pintype "passive"))
      (node (ref "C6") (pin "1") (pinfunction "1_1") (pintype "passive"))
      (node (ref "C7") (pin "1") (pinfunction "1_1") (pintype "passive"))
      (node (ref "C8") (pin "1") (pinfunction "1_1") (pintype "passive"))
      (node (ref "C9") (pin "1") (pinfunction "1_1") (pintype "passive"))
      (node (ref "IC1") (pin "4") (pinfunction "GND_4") (pintype "bidirectional"))
      (node (ref "J1") (pin "21") (pinfunction "21_21") (pintype "passive"))
      (node (ref "J1") (pin "22") (pinfunction "22_22") (pintype "passive"))
      (node (ref "J1") (pin "23") (pinfunction "23_23") (pintype "passive"))
      (node (ref "J1") (pin "24") (pinfunction "24_24") (pintype "passive"))
      (node (ref "J1") (pin "50") (pinfunction "50_50") (pintype "passive"))
      (node (ref "J1") (pin "51") (pinfunction "51_51") (pintype "passive"))
      (node (ref "J1") (pin "52") (pinfunction "52_52") (pintype "passive"))
      (node (ref "J2") (pin "2") (pinfunction "2_2") (pintype "passive"))
      (node (ref "JP1") (pin "2") (pinfunction "2_2") (pintype "passive"))
      (node (ref "R59") (pin "2") (pinfunction "2_2") (pintype "passive"))
      (node (ref "R6") (pin "1") (pinfunction "1_1") (pintype "passive"))
      (node (ref "R62") (pin "2") (pinfunction "2_2") (pintype "passive"))
      (node (ref "R65") (pin "2") (pinfunction "2_2") (pintype "passive"))
      (node (ref "R68") (pin "2") (pinfunction "2_2") (pintype "passive"))
      (node (ref "R71") (pin "2") (pinfunction "2_2") (pintype "passive"))
      (node (ref "U1") (pin "2") (pinfunction "VSS_2") (pintype "passive"))
      (node (ref "U4") (pin "GND@0") (pinfunction "GND_GND@0") (pintype "bidirectional"))
      (node (ref "U4") (pin "GND@1") (pinfunction "GND_GND@1") (pintype "bidirectional"))
      (node (ref "U4") (pin "GND@2") (pinfunction "GND_GND@2") (pintype "bidirectional"))
      (node (ref "U6") (pin "4") (pinfunction "DGND_4") (pintype "power_in"))
      (node (ref "U6") (pin "5") (pinfunction "AGND_5") (pintype "power_in"))
      (node (ref "U7") (pin "4") (pinfunction "DGND_4") (pintype "power_in"))
      (node (ref "U7") (pin "5") (pinfunction "AGND_5") (pintype "power_in"))
      (node (ref "XB1") (pin "1") (pinfunction "GND_1") (pintype "passive"))
      (node (ref "XB1") (pin "10") (pinfunction "GND_10") (pintype "passive"))
      (node (ref "XB1") (pin "12") (pinfunction "GND_12") (pintype "passive"))
      (node (ref "XB1") (pin "21") (pinfunction "GND_21") (pintype "passive"))
      (node (ref "XB1") (pin "32") (pinfunction "GND_32") (pintype "passive"))
      (node (ref "XB1") (pin "34") (pinfunction "GND_34") (pintype "passive"))
    )
    (net (code "109") (name "JOY-CLICK") (class "Default")
      (node (ref "U4") (pin "A4") (pinfunction "A4_A4") (pintype "bidirectional"))
    )
    (net (code "110") (name "JOY-DOWN") (class "Default")
      (node (ref "U4") (pin "A3") (pinfunction "A3_A3") (pintype "bidirectional"))
    )
    (net (code "111") (name "JOY-LEFT") (class "Default")
      (node (ref "U4") (pin "A2") (pinfunction "A2_A2") (pintype "bidirectional"))
    )
    (net (code "112") (name "JOY-RIGHT") (class "Default")
      (node (ref "U4") (pin "A5") (pinfunction "A5_A5") (pintype "bidirectional"))
    )
    (net (code "113") (name "JOY-UP") (class "Default")
      (node (ref "U4") (pin "A1") (pinfunction "A1_A1") (pintype "bidirectional"))
    )
    (net (code "114") (name "LCD") (class "Default")
      (node (ref "U4") (pin "D6") (pinfunction "*D6_D6") (pintype "bidirectional"))
    )
    (net (code "115") (name "LCL") (class "Default")
      (node (ref "IC1") (pin "7") (pinfunction "LY_7") (pintype "bidirectional"))
      (node (ref "J1") (pin "35") (pinfunction "35_35") (pintype "passive"))
      (node (ref "J1") (pin "36") (pinfunction "36_36") (pintype "passive"))
      (node (ref "J1") (pin "37") (pinfunction "37_37") (pintype "passive"))
      (node (ref "J1") (pin "38") (pinfunction "38_38") (pintype "passive"))
      (node (ref "J1") (pin "39") (pinfunction "39_39") (pintype "passive"))
      (node (ref "J1") (pin "40") (pinfunction "40_40") (pintype "passive"))
      (node (ref "J1") (pin "41") (pinfunction "41_41") (pintype "passive"))
      (node (ref "J1") (pin "42") (pinfunction "42_42") (pintype "passive"))
      (node (ref "J1") (pin "43") (pinfunction "43_43") (pintype "passive"))
      (node (ref "J1") (pin "44") (pinfunction "44_44") (pintype "passive"))
      (node (ref "J1") (pin "45") (pinfunction "45_45") (pintype "passive"))
      (node (ref "J1") (pin "46") (pinfunction "46_46") (pintype "passive"))
      (node (ref "J1") (pin "47") (pinfunction "47_47") (pintype "passive"))
      (node (ref "J1") (pin "48") (pinfunction "48_48") (pintype "passive"))
      (node (ref "J1") (pin "49") (pinfunction "49_49") (pintype "passive"))
      (node (ref "J1") (pin "57") (pinfunction "57_57") (pintype "passive"))
      (node (ref "R10") (pin "1") (pinfunction "1_1") (pintype "passive"))
    )
    (net (code "116") (name "LDA") (class "Default")
      (node (ref "IC1") (pin "2") (pinfunction "LX_2") (pintype "bidirectional"))
      (node (ref "J1") (pin "32") (pinfunction "32_32") (pintype "passive"))
      (node (ref "R9") (pin "2") (pinfunction "2_2") (pintype "passive"))
    )
    (net (code "117") (name "LED1") (class "Default")
      (node (ref "U4") (pin "D8") (pinfunction "D8_D8") (pintype "bidirectional"))
    )
    (net (code "118") (name "LED2") (class "Default")
      (node (ref "U4") (pin "D7") (pinfunction "D7_D7") (pintype "bidirectional"))
    )
    (net (code "119") (name "MISO") (class "Default")
      (node (ref "B1") (pin "50") (pinfunction "50_50") (pintype "bidirectional"))
      (node (ref "U4") (pin "D12") (pinfunction "D12_D12") (pintype "bidirectional"))
    )
    (net (code "120") (name "MOSI") (class "Default")
      (node (ref "B1") (pin "51") (pinfunction "51_51") (pintype "bidirectional"))
      (node (ref "U4") (pin "D11") (pinfunction "*D11_D11") (pintype "bidirectional"))
    )
    (net (code "121") (name "Net-(BRAKEPRES-COMMON_ANODE)") (class "Default")
      (node (ref "BRAKEPRES") (pin "1") (pinfunction "COMMON_ANODE_1") (pintype "bidirectional"))
      (node (ref "R15") (pin "1") (pinfunction "1_1") (pintype "passive"))
    )
    (net (code "122") (name "Net-(BRAKETEMP-COMMON_ANODE)") (class "Default")
      (node (ref "BRAKETEMP") (pin "1") (pinfunction "COMMON_ANODE_1") (pintype "bidirectional"))
      (node (ref "R13") (pin "1") (pinfunction "1_1") (pintype "passive"))
    )
    (net (code "123") (name "Net-(COOLANTTEMP-COMMON_ANODE)") (class "Default")
      (node (ref "COOLANTTEMP") (pin "1") (pinfunction "COMMON_ANODE_1") (pintype "bidirectional"))
      (node (ref "R18") (pin "1") (pinfunction "1_1") (pintype "passive"))
    )
    (net (code "124") (name "Net-(DAQ-COMMON_ANODE)") (class "Default")
      (node (ref "DAQ") (pin "1") (pinfunction "COMMON_ANODE_1") (pintype "bidirectional"))
      (node (ref "R23") (pin "1") (pinfunction "1_1") (pintype "passive"))
    )
    (net (code "125") (name "Net-(DASH-COMMON_ANODE)") (class "Default")
      (node (ref "DASH") (pin "1") (pinfunction "COMMON_ANODE_1") (pintype "bidirectional"))
      (node (ref "R11") (pin "1") (pinfunction "1_1") (pintype "passive"))
    )
    (net (code "126") (name "Net-(INTAKEPRES-COMMON_ANODE)") (class "Default")
      (node (ref "INTAKEPRES") (pin "1") (pinfunction "COMMON_ANODE_1") (pintype "bidirectional"))
      (node (ref "R16") (pin "1") (pinfunction "1_1") (pintype "passive"))
    )
    (net (code "127") (name "Net-(INTAKETEMP-COMMON_ANODE)") (class "Default")
      (node (ref "INTAKETEMP") (pin "1") (pinfunction "COMMON_ANODE_1") (pintype "bidirectional"))
      (node (ref "R17") (pin "1") (pinfunction "1_1") (pintype "passive"))
    )
    (net (code "128") (name "Net-(LAMBDAS-COMMON_ANODE)") (class "Default")
      (node (ref "LAMBDAS") (pin "1") (pinfunction "COMMON_ANODE_1") (pintype "bidirectional"))
      (node (ref "R12") (pin "1") (pinfunction "1_1") (pintype "passive"))
    )
    (net (code "129") (name "Net-(OILPRES-COMMON_ANODE)") (class "Default")
      (node (ref "OILPRES") (pin "1") (pinfunction "COMMON_ANODE_1") (pintype "bidirectional"))
      (node (ref "R19") (pin "1") (pinfunction "1_1") (pintype "passive"))
    )
    (net (code "130") (name "Net-(OILTEMP-COMMON_ANODE)") (class "Default")
      (node (ref "OILTEMP") (pin "1") (pinfunction "COMMON_ANODE_1") (pintype "bidirectional"))
      (node (ref "R20") (pin "1") (pinfunction "1_1") (pintype "passive"))
    )
    (net (code "131") (name "Net-(R24-Pad2)") (class "Default")
      (node (ref "R24") (pin "2") (pinfunction "2_2") (pintype "passive"))
      (node (ref "REC") (pin "2") (pinfunction "2_2") (pintype "passive"))
    )
    (net (code "132") (name "Net-(R51-Pad2)") (class "Default")
      (node (ref "R51") (pin "2") (pinfunction "2_2") (pintype "passive"))
      (node (ref "R59") (pin "1") (pinfunction "1_1") (pintype "passive"))
      (node (ref "R60") (pin "2") (pinfunction "2_2") (pintype "passive"))
    )
    (net (code "133") (name "Net-(R53-Pad2)") (class "Default")
      (node (ref "R53") (pin "2") (pinfunction "2_2") (pintype "passive"))
      (node (ref "R62") (pin "1") (pinfunction "1_1") (pintype "passive"))
      (node (ref "R63") (pin "2") (pinfunction "2_2") (pintype "passive"))
    )
    (net (code "134") (name "Net-(R55-Pad2)") (class "Default")
      (node (ref "R55") (pin "2") (pinfunction "2_2") (pintype "passive"))
      (node (ref "R65") (pin "1") (pinfunction "1_1") (pintype "passive"))
      (node (ref "R66") (pin "2") (pinfunction "2_2") (pintype "passive"))
    )
    (net (code "135") (name "Net-(R57-Pad2)") (class "Default")
      (node (ref "R57") (pin "2") (pinfunction "2_2") (pintype "passive"))
      (node (ref "R68") (pin "1") (pinfunction "1_1") (pintype "passive"))
      (node (ref "R69") (pin "2") (pinfunction "2_2") (pintype "passive"))
    )
    (net (code "136") (name "Net-(SHOCKPOT-COMMON_ANODE)") (class "Default")
      (node (ref "R14") (pin "1") (pinfunction "1_1") (pintype "passive"))
      (node (ref "SHOCKPOT") (pin "1") (pinfunction "COMMON_ANODE_1") (pintype "bidirectional"))
    )
    (net (code "137") (name "Net-(SPARE1-COMMON_ANODE)") (class "Default")
      (node (ref "R21") (pin "1") (pinfunction "1_1") (pintype "passive"))
      (node (ref "SPARE1") (pin "1") (pinfunction "COMMON_ANODE_1") (pintype "bidirectional"))
    )
    (net (code "138") (name "Net-(SPARE2-COMMON_ANODE)") (class "Default")
      (node (ref "R22") (pin "1") (pinfunction "1_1") (pintype "passive"))
      (node (ref "SPARE2") (pin "1") (pinfunction "COMMON_ANODE_1") (pintype "bidirectional"))
    )
    (net (code "139") (name "Net-(U1-CE)") (class "Default")
      (node (ref "R5") (pin "2") (pinfunction "2_2") (pintype "passive"))
      (node (ref "R6") (pin "2") (pinfunction "2_2") (pintype "passive"))
      (node (ref "U1") (pin "3") (pinfunction "CE_3") (pintype "passive"))
    )
    (net (code "140") (name "Net-(U6-DRDY_N)") (class "Default")
      (node (ref "R43") (pin "1") (pinfunction "1_1") (pintype "passive"))
      (node (ref "U6") (pin "14") (pinfunction "DRDY_N_14") (pintype "output"))
    )
    (net (code "141") (name "Net-(U6-REFN)") (class "Default")
      (node (ref "R42") (pin "2") (pinfunction "2_2") (pintype "passive"))
      (node (ref "U6") (pin "8") (pinfunction "REFN_8") (pintype "input"))
    )
    (net (code "142") (name "Net-(U6-REFP)") (class "Default")
      (node (ref "R41") (pin "2") (pinfunction "2_2") (pintype "passive"))
      (node (ref "U6") (pin "9") (pinfunction "REFP_9") (pintype "input"))
    )
    (net (code "143") (name "Net-(U7-DRDY_N)") (class "Default")
      (node (ref "R46") (pin "1") (pinfunction "1_1") (pintype "passive"))
      (node (ref "U7") (pin "14") (pinfunction "DRDY_N_14") (pintype "output"))
    )
    (net (code "144") (name "Net-(U7-REFN)") (class "Default")
      (node (ref "R45") (pin "2") (pinfunction "2_2") (pintype "passive"))
      (node (ref "U7") (pin "8") (pinfunction "REFN_8") (pintype "input"))
    )
    (net (code "145") (name "Net-(U7-REFP)") (class "Default")
      (node (ref "R44") (pin "2") (pinfunction "2_2") (pintype "passive"))
      (node (ref "U7") (pin "9") (pinfunction "REFP_9") (pintype "input"))
    )
    (net (code "146") (name "Net-(XB1-D\\T\\R\\{slash}DIO8)") (class "Default")
      (node (ref "R8") (pin "2") (pinfunction "2_2") (pintype "passive"))
      (node (ref "XB1") (pin "9") (pinfunction "D\\T\\R\\/DIO8_9") (pintype "passive"))
    )
    (net (code "147") (name "Net-(XB1-R\\T\\S\\{slash}DIO6)") (class "Default")
      (node (ref "R7") (pin "1") (pinfunction "1_1") (pintype "passive"))
      (node (ref "XB1") (pin "27") (pinfunction "R\\T\\S\\/DIO6_27") (pintype "passive"))
    )
    (net (code "148") (name "Net-(XB1-VCC)") (class "Default")
      (node (ref "C3") (pin "2") (pinfunction "2_2") (pintype "passive"))
      (node (ref "C4") (pin "2") (pinfunction "2_2") (pintype "passive"))
      (node (ref "C5") (pin "2") (pinfunction "2_2") (pintype "passive"))
      (node (ref "XB1") (pin "2") (pinfunction "VCC_2") (pintype "passive"))
    )
    (net (code "149") (name "REC") (class "Default")
      (node (ref "B1") (pin "11") (pinfunction "11_11") (pintype "bidirectional"))
      (node (ref "J1") (pin "33") (pinfunction "33_33") (pintype "passive"))
      (node (ref "R49") (pin "2") (pinfunction "2_2") (pintype "passive"))
      (node (ref "REC") (pin "1") (pinfunction "1_1") (pintype "passive"))
    )
    (net (code "150") (name "RS") (class "Default")
      (node (ref "U4") (pin "RES") (pinfunction "RES_RES") (pintype "bidirectional"))
    )
    (net (code "151") (name "RX") (class "Default")
      (node (ref "U4") (pin "RX") (pinfunction "RX_RX") (pintype "bidirectional"))
    )
    (net (code "152") (name "RX0") (class "Default")
      (node (ref "B1") (pin "0") (pinfunction "0(RX0)_0") (pintype "bidirectional"))
      (node (ref "Q2") (pin "3") (pinfunction "D_3") (pintype "passive"))
      (node (ref "R2") (pin "1") (pinfunction "1_1") (pintype "passive"))
    )
    (net (code "153") (name "SCK") (class "Default")
      (node (ref "B1") (pin "52") (pinfunction "52_52") (pintype "bidirectional"))
      (node (ref "U4") (pin "D13") (pinfunction "D13_D13") (pintype "bidirectional"))
    )
    (net (code "154") (name "SCL") (class "Default")
      (node (ref "B1") (pin "21") (pinfunction "21(SCL)_21") (pintype "bidirectional"))
      (node (ref "IC1") (pin "6") (pinfunction "SY_6") (pintype "bidirectional"))
      (node (ref "U6") (pin "16") (pinfunction "SCL_16") (pintype "input"))
      (node (ref "U6") (pin "2") (pinfunction "A1_2") (pintype "input"))
      (node (ref "U7") (pin "1") (pinfunction "A0_1") (pintype "input"))
      (node (ref "U7") (pin "16") (pinfunction "SCL_16") (pintype "input"))
    )
    (net (code "155") (name "SDA") (class "Default")
      (node (ref "B1") (pin "20") (pinfunction "20(SDA)_20") (pintype "bidirectional"))
      (node (ref "IC1") (pin "3") (pinfunction "SX_3") (pintype "bidirectional"))
      (node (ref "U6") (pin "1") (pinfunction "A0_1") (pintype "input"))
      (node (ref "U6") (pin "15") (pinfunction "SDA_15") (pintype "bidirectional"))
      (node (ref "U7") (pin "15") (pinfunction "SDA_15") (pintype "bidirectional"))
      (node (ref "U7") (pin "2") (pinfunction "A1_2") (pintype "input"))
    )
    (net (code "156") (name "SD_CS") (class "Default")
      (node (ref "B1") (pin "53") (pinfunction "53_53") (pintype "bidirectional"))
      (node (ref "U4") (pin "D9") (pinfunction "*D9_D9") (pintype "bidirectional"))
    )
    (net (code "157") (name "SG_11") (class "Default")
      (node (ref "J1") (pin "30") (pinfunction "30_30") (pintype "passive"))
      (node (ref "R58") (pin "2") (pinfunction "2_2") (pintype "passive"))
      (node (ref "R70") (pin "2") (pinfunction "2_2") (pintype "passive"))
    )
    (net (code "158") (name "SG_21") (class "Default")
      (node (ref "J1") (pin "29") (pinfunction "29_29") (pintype "passive"))
      (node (ref "R56") (pin "2") (pinfunction "2_2") (pintype "passive"))
      (node (ref "R67") (pin "2") (pinfunction "2_2") (pintype "passive"))
    )
    (net (code "159") (name "SG_31") (class "Default")
      (node (ref "J1") (pin "28") (pinfunction "28_28") (pintype "passive"))
      (node (ref "R54") (pin "2") (pinfunction "2_2") (pintype "passive"))
      (node (ref "R64") (pin "2") (pinfunction "2_2") (pintype "passive"))
    )
    (net (code "160") (name "SG_41") (class "Default")
      (node (ref "J1") (pin "27") (pinfunction "27_27") (pintype "passive"))
      (node (ref "R52") (pin "2") (pinfunction "2_2") (pintype "passive"))
      (node (ref "R61") (pin "2") (pinfunction "2_2") (pintype "passive"))
    )
    (net (code "161") (name "TX") (class "Default")
      (node (ref "U4") (pin "TX") (pinfunction "TX_TX") (pintype "bidirectional"))
    )
    (net (code "162") (name "TX0") (class "Default")
      (node (ref "B1") (pin "1") (pinfunction "1(TX0)_1") (pintype "bidirectional"))
      (node (ref "Q1") (pin "3") (pinfunction "D_3") (pintype "passive"))
      (node (ref "R4") (pin "1") (pinfunction "1_1") (pintype "passive"))
    )
    (net (code "163") (name "unconnected-(B1-5V-Pad5V@1)") (class "Default")
      (node (ref "B1") (pin "5V@1") (pinfunction "5V_5V@1") (pintype "bidirectional"))
    )
    (net (code "164") (name "unconnected-(B1-5V-Pad5V@2)") (class "Default")
      (node (ref "B1") (pin "5V@2") (pinfunction "5V_5V@2") (pintype "bidirectional"))
    )
    (net (code "165") (name "unconnected-(B1-GND-PadGND@1)") (class "Default")
      (node (ref "B1") (pin "GND@1") (pinfunction "GND_GND@1") (pintype "bidirectional"))
    )
    (net (code "166") (name "unconnected-(B1-GND-PadGND@2)") (class "Default")
      (node (ref "B1") (pin "GND@2") (pinfunction "GND_GND@2") (pintype "bidirectional"))
    )
    (net (code "167") (name "unconnected-(B1-GND-PadGND@3)") (class "Default")
      (node (ref "B1") (pin "GND@3") (pinfunction "GND_GND@3") (pintype "bidirectional"))
    )
    (net (code "168") (name "unconnected-(B1-GND-PadGND@4)") (class "Default")
      (node (ref "B1") (pin "GND@4") (pinfunction "GND_GND@4") (pintype "bidirectional"))
    )
    (net (code "169") (name "unconnected-(B1-Pad3.3V)") (class "Default")
      (node (ref "B1") (pin "3.3V") (pinfunction "3.3V_3.3V") (pintype "bidirectional"))
    )
    (net (code "170") (name "unconnected-(B1-Pad12)") (class "Default")
      (node (ref "B1") (pin "12") (pinfunction "12_12") (pintype "bidirectional"))
    )
    (net (code "171") (name "unconnected-(B1-PadAREF)") (class "Default")
      (node (ref "B1") (pin "AREF") (pinfunction "AREF_AREF") (pintype "bidirectional"))
    )
    (net (code "172") (name "unconnected-(B1-PadRESET)") (class "Default")
      (node (ref "B1") (pin "RESET") (pinfunction "RESET_RESET") (pintype "bidirectional"))
    )
    (net (code "173") (name "unconnected-(IC1-NC_1-Pad1)") (class "Default")
      (node (ref "IC1") (pin "1") (pinfunction "NC_1_1") (pintype "bidirectional"))
    )
    (net (code "174") (name "unconnected-(IC1-NC_2-Pad5)") (class "Default")
      (node (ref "IC1") (pin "5") (pinfunction "NC_2_5") (pintype "bidirectional"))
    )
    (net (code "175") (name "unconnected-(J1-Pad2)") (class "Default")
      (node (ref "J1") (pin "2") (pinfunction "2_2") (pintype "passive"))
    )
    (net (code "176") (name "unconnected-(J1-Pad3)") (class "Default")
      (node (ref "J1") (pin "3") (pinfunction "3_3") (pintype "passive"))
    )
    (net (code "177") (name "unconnected-(J1-Pad55)") (class "Default")
      (node (ref "J1") (pin "55") (pinfunction "55_55") (pintype "passive"))
    )
    (net (code "178") (name "unconnected-(J1-Pad56)") (class "Default")
      (node (ref "J1") (pin "56") (pinfunction "56_56") (pintype "passive"))
    )
    (net (code "179") (name "unconnected-(J1-Pad58)") (class "Default")
      (node (ref "J1") (pin "58") (pinfunction "58_58") (pintype "passive"))
    )
    (net (code "180") (name "unconnected-(J1-Pad59)") (class "Default")
      (node (ref "J1") (pin "59") (pinfunction "59_59") (pintype "passive"))
    )
    (net (code "181") (name "unconnected-(U1-NC-Pad4)") (class "Default")
      (node (ref "U1") (pin "4") (pinfunction "NC_4") (pintype "no_connect"))
    )
    (net (code "182") (name "unconnected-(U4-Pad3.3V)") (class "Default")
      (node (ref "U4") (pin "3.3V") (pinfunction "3.3V_3.3V") (pintype "bidirectional"))
    )
    (net (code "183") (name "unconnected-(U4-PadA0)") (class "Default")
      (node (ref "U4") (pin "A0") (pinfunction "A0_A0") (pintype "bidirectional"))
    )
    (net (code "184") (name "unconnected-(U4-PadIOREF)") (class "Default")
      (node (ref "U4") (pin "IOREF") (pinfunction "IOREF_IOREF") (pintype "bidirectional"))
    )
    (net (code "185") (name "unconnected-(U4-PadSCL)") (class "Default")
      (node (ref "U4") (pin "SCL") (pinfunction "SCL_SCL") (pintype "bidirectional"))
    )
    (net (code "186") (name "unconnected-(U4-PadSDA)") (class "Default")
      (node (ref "U4") (pin "SDA") (pinfunction "SDA_SDA") (pintype "bidirectional"))
    )
    (net (code "187") (name "unconnected-(U4-PadVIN)") (class "Default")
      (node (ref "U4") (pin "VIN") (pinfunction "VIN_VIN") (pintype "bidirectional"))
    )
    (net (code "188") (name "unconnected-(XB1-AD1{slash}DIO1-Pad30)") (class "Default")
      (node (ref "XB1") (pin "30") (pinfunction "AD1/DIO1_30") (pintype "passive"))
    )
    (net (code "189") (name "unconnected-(XB1-AD2{slash}DIO2-Pad29)") (class "Default")
      (node (ref "XB1") (pin "29") (pinfunction "AD2/DIO2_29") (pintype "passive"))
    )
    (net (code "190") (name "unconnected-(XB1-AD3{slash}DIO3-Pad28)") (class "Default")
      (node (ref "XB1") (pin "28") (pinfunction "AD3/DIO3_28") (pintype "passive"))
    )
    (net (code "191") (name "unconnected-(XB1-ASSOC{slash}DIO5-Pad26)") (class "Default")
      (node (ref "XB1") (pin "26") (pinfunction "ASSOC/DIO5_26") (pintype "passive"))
    )
    (net (code "192") (name "unconnected-(XB1-A\\T\\T\\N\\{slash}DIO19-Pad11)") (class "Default")
      (node (ref "XB1") (pin "11") (pinfunction "A\\T\\T\\N\\/DIO19_11") (pintype "passive"))
    )
    (net (code "193") (name "unconnected-(XB1-COMM{slash}AD0{slash}DIO0-Pad31)") (class "Default")
      (node (ref "XB1") (pin "31") (pinfunction "COMM/AD0/DIO0_31") (pintype "passive"))
    )
    (net (code "194") (name "unconnected-(XB1-C\\T\\S\\{slash}DIO7-Pad24)") (class "Default")
      (node (ref "XB1") (pin "24") (pinfunction "C\\T\\S\\/DIO7_24") (pintype "passive"))
    )
    (net (code "195") (name "unconnected-(XB1-DIO4-Pad23)") (class "Default")
      (node (ref "XB1") (pin "23") (pinfunction "DIO4_23") (pintype "passive"))
    )
    (net (code "196") (name "unconnected-(XB1-DIO12-Pad5)") (class "Default")
      (node (ref "XB1") (pin "5") (pinfunction "DIO12_5") (pintype "passive"))
    )
    (net (code "197") (name "unconnected-(XB1-NC-Pad17)") (class "Default")
      (node (ref "XB1") (pin "17") (pinfunction "NC_17") (pintype "passive"))
    )
    (net (code "198") (name "unconnected-(XB1-NC-Pad18)") (class "Default")
      (node (ref "XB1") (pin "18") (pinfunction "NC_18") (pintype "passive"))
    )
    (net (code "199") (name "unconnected-(XB1-NC-Pad19)") (class "Default")
      (node (ref "XB1") (pin "19") (pinfunction "NC_19") (pintype "passive"))
    )
    (net (code "200") (name "unconnected-(XB1-NC-Pad20)") (class "Default")
      (node (ref "XB1") (pin "20") (pinfunction "NC_20") (pintype "passive"))
    )
    (net (code "201") (name "unconnected-(XB1-NC-Pad22)") (class "Default")
      (node (ref "XB1") (pin "22") (pinfunction "NC_22") (pintype "passive"))
    )
    (net (code "202") (name "unconnected-(XB1-ON{slash}S\\L\\P\\{slash}DIO9-Pad25)") (class "Default")
      (node (ref "XB1") (pin "25") (pinfunction "ON/S\\L\\P\\/DIO9_25") (pintype "passive"))
    )
    (net (code "203") (name "unconnected-(XB1-PWM0{slash}RSSI{slash}DIO10-Pad7)") (class "Default")
      (node (ref "XB1") (pin "7") (pinfunction "PWM0/RSSI/DIO10_7") (pintype "passive"))
    )
    (net (code "204") (name "unconnected-(XB1-PWM1{slash}DIO11-Pad8)") (class "Default")
      (node (ref "XB1") (pin "8") (pinfunction "PWM1/DIO11_8") (pintype "passive"))
    )
    (net (code "205") (name "unconnected-(XB1-RF-Pad33)") (class "Default")
      (node (ref "XB1") (pin "33") (pinfunction "RF_33") (pintype "passive"))
    )
    (net (code "206") (name "unconnected-(XB1-SPI_MISO{slash}DIO15-Pad16)") (class "Default")
      (node (ref "XB1") (pin "16") (pinfunction "SPI_MISO/DIO15_16") (pintype "passive"))
    )
    (net (code "207") (name "unconnected-(XB1-SPI_MOSI{slash}DIO16-Pad15)") (class "Default")
      (node (ref "XB1") (pin "15") (pinfunction "SPI_MOSI/DIO16_15") (pintype "passive"))
    )
    (net (code "208") (name "unconnected-(XB1-SPI_SCLK{slash}DIO18-Pad13)") (class "Default")
      (node (ref "XB1") (pin "13") (pinfunction "SPI_SCLK/DIO18_13") (pintype "passive"))
    )
    (net (code "209") (name "unconnected-(XB1-SPI_S\\S\\E\\L\\{slash}DIO17-Pad14)") (class "Default")
      (node (ref "XB1") (pin "14") (pinfunction "SPI_S\\S\\E\\L\\/DIO17_14") (pintype "passive"))
    )
    (net (code "210") (name "unconnected-(XB1-\\R\\E\\S\\E\\T\\-Pad6)") (class "Default")
      (node (ref "XB1") (pin "6") (pinfunction "\\R\\E\\S\\E\\T\\_6") (pintype "passive"))
    )
  )
)
